# jr-support_v3.net
KiCad netlist of a schematic drawn in EAGLE
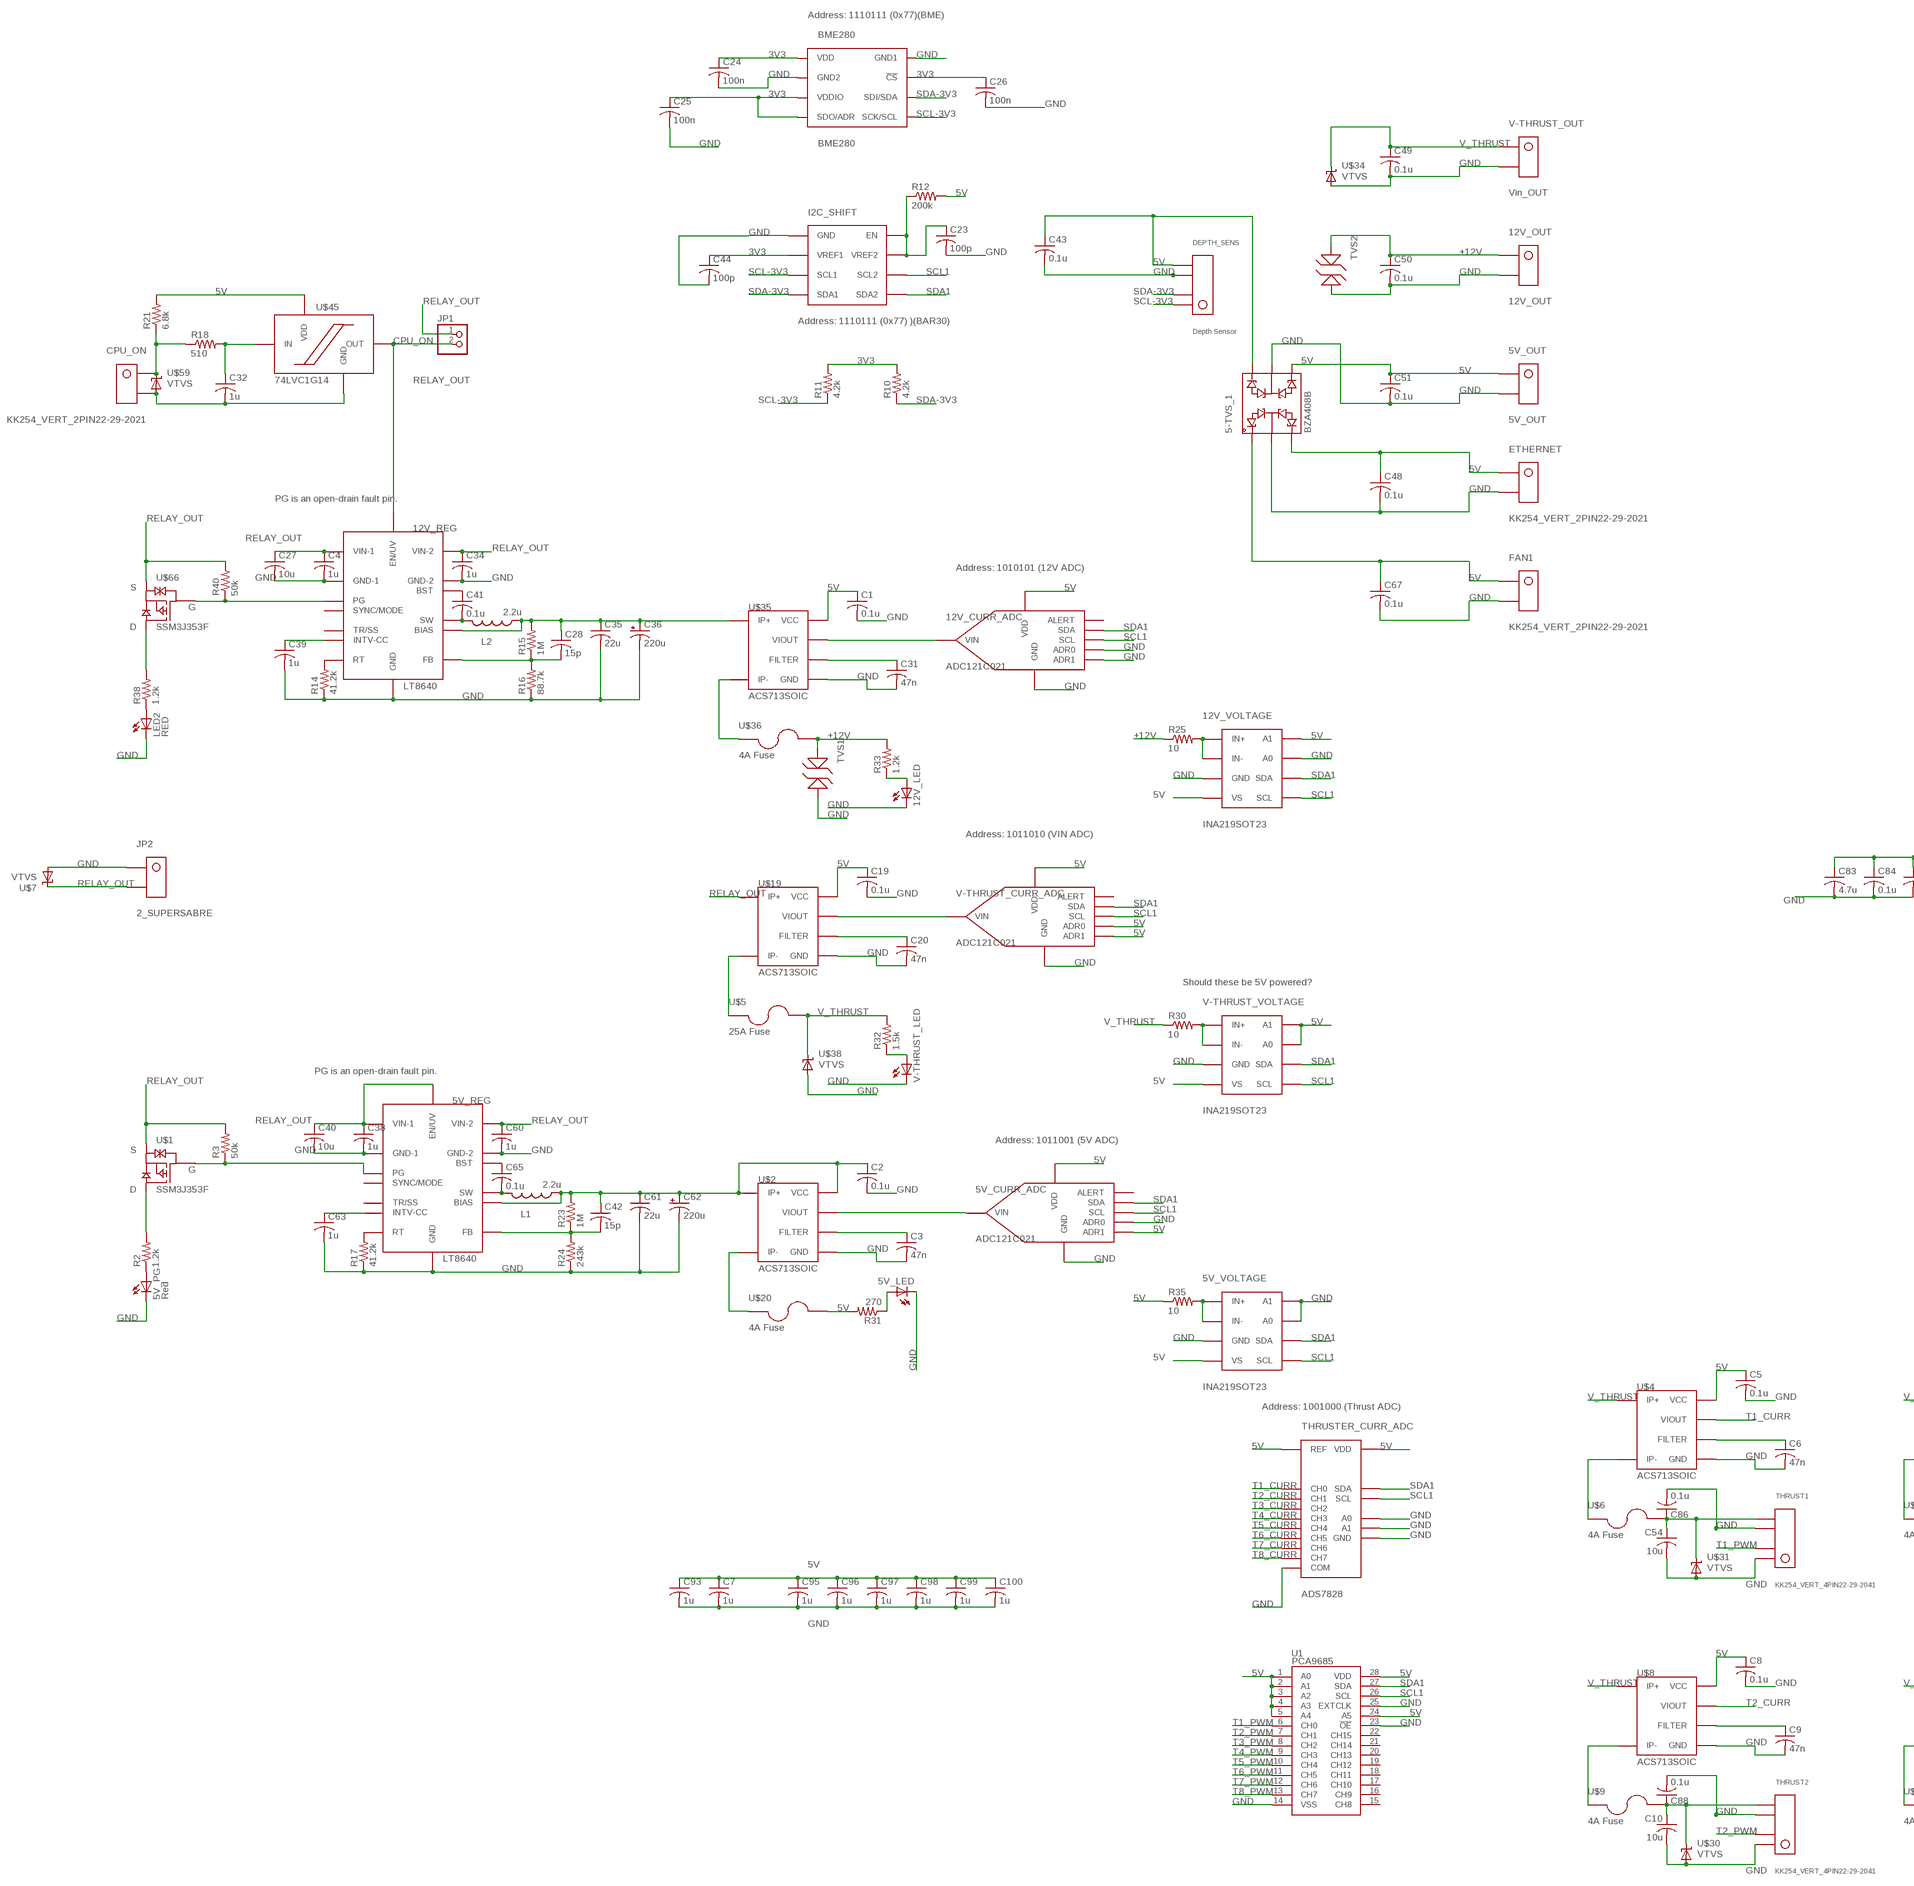
[diagram p0: schematic, sheet 1, part 1 of 2]
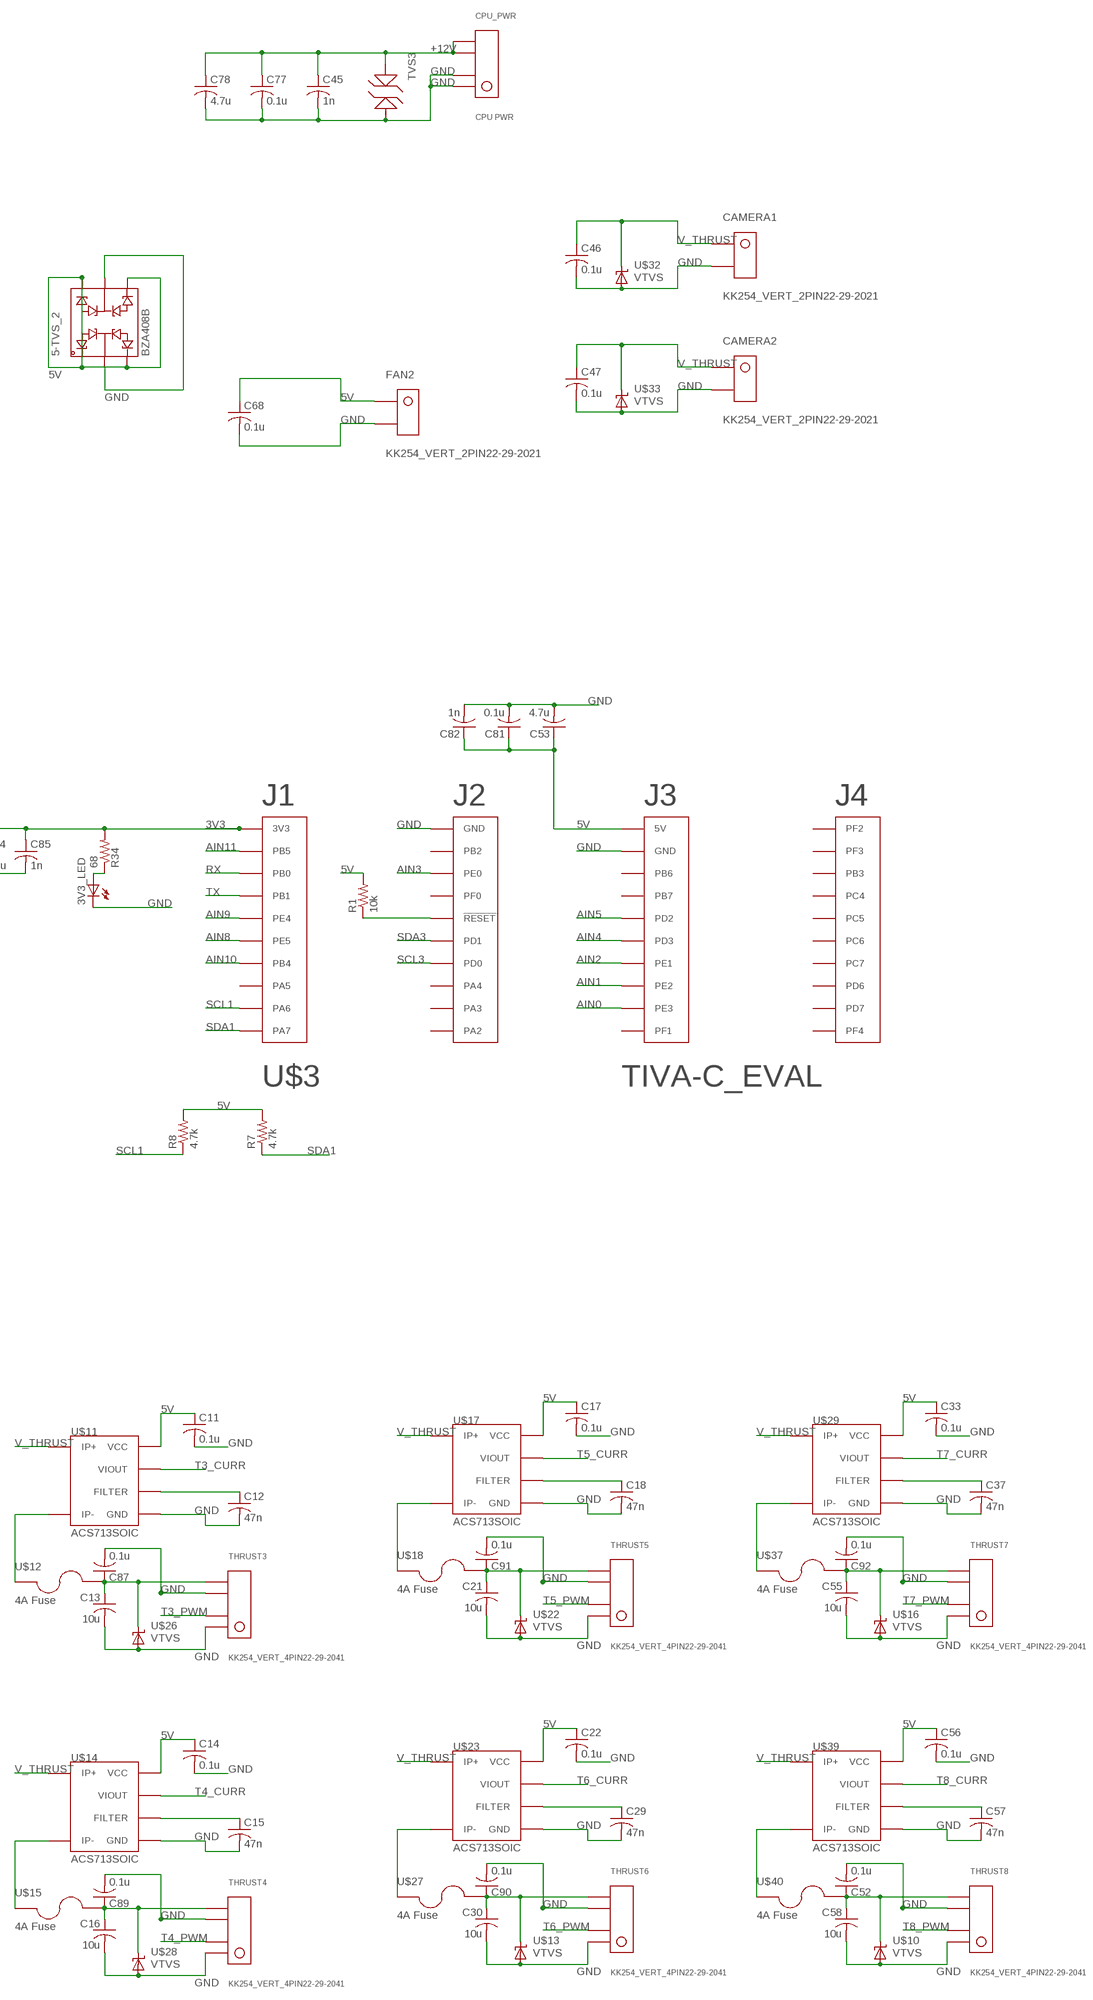
[diagram p1: schematic, sheet 1, part 2 of 2]

(export (version "E")
  (design (tool "Eeschema 10.0.6"))
  (components
    (comp (ref "3V3_LED")
      (value "0805_LED")
      (footprint "eagle-import:0805")
      (libsource (lib "eagle-import") (part "0805_LED"))
    )
    (comp (ref "5-TVS_1")
      (value "BZA408B")
      (footprint "eagle-import:SOT457")
      (libsource (lib "eagle-import") (part "BZA408B"))
    )
    (comp (ref "5-TVS_2")
      (value "BZA408B")
      (footprint "eagle-import:SOT457")
      (libsource (lib "eagle-import") (part "BZA408B"))
    )
    (comp (ref "5V_CURR_ADC")
      (value "ADC121C021")
      (footprint "eagle-import:VSSOP-8")
      (libsource (lib "eagle-import") (part "ADC121C021"))
    )
    (comp (ref "5V_LED")
      (value "0805_LED")
      (footprint "eagle-import:0805")
      (libsource (lib "eagle-import") (part "0805_LED"))
    )
    (comp (ref "5V_OUT")
      (value "5V_OUT")
      (footprint "eagle-import:KK254_VERT_2PIN")
      (libsource (lib "eagle-import") (part "KK254_VERT_2PIN22-29-2021"))
    )
    (comp (ref "5V_PG")
      (value "Red")
      (footprint "eagle-import:CHIP-LED0805")
      (libsource (lib "eagle-import") (part "LEDCHIP-LED0805"))
    )
    (comp (ref "5V_REG")
      (value "LT8640")
      (footprint "eagle-import:QFN18-3X4")
      (libsource (lib "eagle-import") (part "LT8640"))
    )
    (comp (ref "5V_VOLTAGE")
      (value "INA219SOT23")
      (footprint "eagle-import:SOT-23-8")
      (libsource (lib "eagle-import") (part "INA219SOT23"))
    )
    (comp (ref "12V_CURR_ADC")
      (value "ADC121C021")
      (footprint "eagle-import:VSSOP-8")
      (libsource (lib "eagle-import") (part "ADC121C021"))
    )
    (comp (ref "12V_LED")
      (value "0805_LED")
      (footprint "eagle-import:0805")
      (libsource (lib "eagle-import") (part "0805_LED"))
    )
    (comp (ref "12V_OUT")
      (value "12V_OUT")
      (footprint "eagle-import:KK254_VERT_2PIN")
      (libsource (lib "eagle-import") (part "KK254_VERT_2PIN22-29-2021"))
    )
    (comp (ref "12V_REG")
      (value "LT8640")
      (footprint "eagle-import:QFN18-3X4")
      (libsource (lib "eagle-import") (part "LT8640"))
    )
    (comp (ref "12V_VOLTAGE")
      (value "INA219SOT23")
      (footprint "eagle-import:SOT-23-8")
      (libsource (lib "eagle-import") (part "INA219SOT23"))
    )
    (comp (ref "BME280")
      (value "BME280")
      (footprint "eagle-import:BME280_LGA")
      (libsource (lib "eagle-import") (part "BME280"))
    )
    (comp (ref "C1")
      (value "0.1u")
      (footprint "eagle-import:C0805")
      (libsource (lib "eagle-import") (part "C-USC0805"))
    )
    (comp (ref "C2")
      (value "0.1u")
      (footprint "eagle-import:C0805")
      (libsource (lib "eagle-import") (part "C-USC0805"))
    )
    (comp (ref "C3")
      (value "47n")
      (footprint "eagle-import:C0805")
      (libsource (lib "eagle-import") (part "C-USC0805"))
    )
    (comp (ref "C4")
      (value "1u")
      (footprint "eagle-import:C0805")
      (libsource (lib "eagle-import") (part "C-USC0805"))
    )
    (comp (ref "C5")
      (value "0.1u")
      (footprint "eagle-import:C0805")
      (libsource (lib "eagle-import") (part "C-USC0805"))
    )
    (comp (ref "C6")
      (value "47n")
      (footprint "eagle-import:C0805")
      (libsource (lib "eagle-import") (part "C-USC0805"))
    )
    (comp (ref "C7")
      (value "1u")
      (footprint "eagle-import:C0805")
      (libsource (lib "eagle-import") (part "C-USC0805"))
    )
    (comp (ref "C8")
      (value "0.1u")
      (footprint "eagle-import:C0805")
      (libsource (lib "eagle-import") (part "C-USC0805"))
    )
    (comp (ref "C9")
      (value "47n")
      (footprint "eagle-import:C0805")
      (libsource (lib "eagle-import") (part "C-USC0805"))
    )
    (comp (ref "C10")
      (value "10u")
      (footprint "eagle-import:C0805")
      (libsource (lib "eagle-import") (part "C-USC0805"))
    )
    (comp (ref "C11")
      (value "0.1u")
      (footprint "eagle-import:C0805")
      (libsource (lib "eagle-import") (part "C-USC0805"))
    )
    (comp (ref "C12")
      (value "47n")
      (footprint "eagle-import:C0805")
      (libsource (lib "eagle-import") (part "C-USC0805"))
    )
    (comp (ref "C13")
      (value "10u")
      (footprint "eagle-import:C0805")
      (libsource (lib "eagle-import") (part "C-USC0805"))
    )
    (comp (ref "C14")
      (value "0.1u")
      (footprint "eagle-import:C0805")
      (libsource (lib "eagle-import") (part "C-USC0805"))
    )
    (comp (ref "C15")
      (value "47n")
      (footprint "eagle-import:C0805")
      (libsource (lib "eagle-import") (part "C-USC0805"))
    )
    (comp (ref "C16")
      (value "10u")
      (footprint "eagle-import:C0805")
      (libsource (lib "eagle-import") (part "C-USC0805"))
    )
    (comp (ref "C17")
      (value "0.1u")
      (footprint "eagle-import:C0805")
      (libsource (lib "eagle-import") (part "C-USC0805"))
    )
    (comp (ref "C18")
      (value "47n")
      (footprint "eagle-import:C0805")
      (libsource (lib "eagle-import") (part "C-USC0805"))
    )
    (comp (ref "C19")
      (value "0.1u")
      (footprint "eagle-import:C0805")
      (libsource (lib "eagle-import") (part "C-USC0805"))
    )
    (comp (ref "C20")
      (value "47n")
      (footprint "eagle-import:C0805")
      (libsource (lib "eagle-import") (part "C-USC0805"))
    )
    (comp (ref "C21")
      (value "10u")
      (footprint "eagle-import:C0805")
      (libsource (lib "eagle-import") (part "C-USC0805"))
    )
    (comp (ref "C22")
      (value "0.1u")
      (footprint "eagle-import:C0805")
      (libsource (lib "eagle-import") (part "C-USC0805"))
    )
    (comp (ref "C23")
      (value "100p")
      (footprint "eagle-import:C0805")
      (libsource (lib "eagle-import") (part "C-USC0805"))
    )
    (comp (ref "C24")
      (value "100n")
      (footprint "eagle-import:C0805")
      (libsource (lib "eagle-import") (part "C-USC0805"))
    )
    (comp (ref "C25")
      (value "100n")
      (footprint "eagle-import:C0805")
      (libsource (lib "eagle-import") (part "C-USC0805"))
    )
    (comp (ref "C26")
      (value "100n")
      (footprint "eagle-import:C0805")
      (libsource (lib "eagle-import") (part "C-USC0805"))
    )
    (comp (ref "C27")
      (value "10u")
      (footprint "eagle-import:C0805")
      (libsource (lib "eagle-import") (part "C-USC0805"))
    )
    (comp (ref "C28")
      (value "15p")
      (footprint "eagle-import:C0805")
      (libsource (lib "eagle-import") (part "C-USC0805"))
    )
    (comp (ref "C29")
      (value "47n")
      (footprint "eagle-import:C0805")
      (libsource (lib "eagle-import") (part "C-USC0805"))
    )
    (comp (ref "C30")
      (value "10u")
      (footprint "eagle-import:C0805")
      (libsource (lib "eagle-import") (part "C-USC0805"))
    )
    (comp (ref "C31")
      (value "47n")
      (footprint "eagle-import:C0805")
      (libsource (lib "eagle-import") (part "C-USC0805"))
    )
    (comp (ref "C32")
      (value "1u")
      (footprint "eagle-import:C0805")
      (libsource (lib "eagle-import") (part "C-USC0805"))
    )
    (comp (ref "C33")
      (value "0.1u")
      (footprint "eagle-import:C0805")
      (libsource (lib "eagle-import") (part "C-USC0805"))
    )
    (comp (ref "C34")
      (value "1u")
      (footprint "eagle-import:C0805")
      (libsource (lib "eagle-import") (part "C-USC0805"))
    )
    (comp (ref "C35")
      (value "22u")
      (footprint "eagle-import:C0805")
      (libsource (lib "eagle-import") (part "C-USC0805"))
    )
    (comp (ref "C36")
      (value "220u")
      (footprint "eagle-import:C-F80")
      (libsource (lib "eagle-import") (part "CPOL-USC-F80"))
    )
    (comp (ref "C37")
      (value "47n")
      (footprint "eagle-import:C0805")
      (libsource (lib "eagle-import") (part "C-USC0805"))
    )
    (comp (ref "C38")
      (value "1u")
      (footprint "eagle-import:C0805")
      (libsource (lib "eagle-import") (part "C-USC0805"))
    )
    (comp (ref "C39")
      (value "1u")
      (footprint "eagle-import:C0805")
      (libsource (lib "eagle-import") (part "C-USC0805"))
    )
    (comp (ref "C40")
      (value "10u")
      (footprint "eagle-import:C0805")
      (libsource (lib "eagle-import") (part "C-USC0805"))
    )
    (comp (ref "C41")
      (value "0.1u")
      (footprint "eagle-import:C0805")
      (libsource (lib "eagle-import") (part "C-USC0805"))
    )
    (comp (ref "C42")
      (value "15p")
      (footprint "eagle-import:C0805")
      (libsource (lib "eagle-import") (part "C-USC0805"))
    )
    (comp (ref "C43")
      (value "0.1u")
      (footprint "eagle-import:C0805")
      (libsource (lib "eagle-import") (part "C-USC0805"))
    )
    (comp (ref "C44")
      (value "100p")
      (footprint "eagle-import:C0805")
      (libsource (lib "eagle-import") (part "C-USC0805"))
    )
    (comp (ref "C45")
      (value "1n")
      (footprint "eagle-import:C0805")
      (libsource (lib "eagle-import") (part "C-USC0805"))
    )
    (comp (ref "C46")
      (value "0.1u")
      (footprint "eagle-import:C0805")
      (libsource (lib "eagle-import") (part "C-USC0805"))
    )
    (comp (ref "C47")
      (value "0.1u")
      (footprint "eagle-import:C0805")
      (libsource (lib "eagle-import") (part "C-USC0805"))
    )
    (comp (ref "C48")
      (value "0.1u")
      (footprint "eagle-import:C0805")
      (libsource (lib "eagle-import") (part "C-USC0805"))
    )
    (comp (ref "C49")
      (value "0.1u")
      (footprint "eagle-import:C0805")
      (libsource (lib "eagle-import") (part "C-USC0805"))
    )
    (comp (ref "C50")
      (value "0.1u")
      (footprint "eagle-import:C0805")
      (libsource (lib "eagle-import") (part "C-USC0805"))
    )
    (comp (ref "C51")
      (value "0.1u")
      (footprint "eagle-import:C0805")
      (libsource (lib "eagle-import") (part "C-USC0805"))
    )
    (comp (ref "C52")
      (value "0.1u")
      (footprint "eagle-import:C0805")
      (libsource (lib "eagle-import") (part "C-USC0805"))
    )
    (comp (ref "C53")
      (value "4.7u")
      (footprint "eagle-import:C0805")
      (libsource (lib "eagle-import") (part "C-USC0805"))
    )
    (comp (ref "C54")
      (value "10u")
      (footprint "eagle-import:C0805")
      (libsource (lib "eagle-import") (part "C-USC0805"))
    )
    (comp (ref "C55")
      (value "10u")
      (footprint "eagle-import:C0805")
      (libsource (lib "eagle-import") (part "C-USC0805"))
    )
    (comp (ref "C56")
      (value "0.1u")
      (footprint "eagle-import:C0805")
      (libsource (lib "eagle-import") (part "C-USC0805"))
    )
    (comp (ref "C57")
      (value "47n")
      (footprint "eagle-import:C0805")
      (libsource (lib "eagle-import") (part "C-USC0805"))
    )
    (comp (ref "C58")
      (value "10u")
      (footprint "eagle-import:C0805")
      (libsource (lib "eagle-import") (part "C-USC0805"))
    )
    (comp (ref "C60")
      (value "1u")
      (footprint "eagle-import:C0805")
      (libsource (lib "eagle-import") (part "C-USC0805"))
    )
    (comp (ref "C61")
      (value "22u")
      (footprint "eagle-import:C0805")
      (libsource (lib "eagle-import") (part "C-USC0805"))
    )
    (comp (ref "C62")
      (value "220u")
      (footprint "eagle-import:C-F80")
      (libsource (lib "eagle-import") (part "CPOL-USC-F80"))
    )
    (comp (ref "C63")
      (value "1u")
      (footprint "eagle-import:C0805")
      (libsource (lib "eagle-import") (part "C-USC0805"))
    )
    (comp (ref "C65")
      (value "0.1u")
      (footprint "eagle-import:C0805")
      (libsource (lib "eagle-import") (part "C-USC0805"))
    )
    (comp (ref "C67")
      (value "0.1u")
      (footprint "eagle-import:C0805")
      (libsource (lib "eagle-import") (part "C-USC0805"))
    )
    (comp (ref "C68")
      (value "0.1u")
      (footprint "eagle-import:C0805")
      (libsource (lib "eagle-import") (part "C-USC0805"))
    )
    (comp (ref "C77")
      (value "0.1u")
      (footprint "eagle-import:C0805")
      (libsource (lib "eagle-import") (part "C-USC0805"))
    )
    (comp (ref "C78")
      (value "4.7u")
      (footprint "eagle-import:C0805")
      (libsource (lib "eagle-import") (part "C-USC0805"))
    )
    (comp (ref "C81")
      (value "0.1u")
      (footprint "eagle-import:C0805")
      (libsource (lib "eagle-import") (part "C-USC0805"))
    )
    (comp (ref "C82")
      (value "1n")
      (footprint "eagle-import:C0805")
      (libsource (lib "eagle-import") (part "C-USC0805"))
    )
    (comp (ref "C83")
      (value "4.7u")
      (footprint "eagle-import:C0805")
      (libsource (lib "eagle-import") (part "C-USC0805"))
    )
    (comp (ref "C84")
      (value "0.1u")
      (footprint "eagle-import:C0805")
      (libsource (lib "eagle-import") (part "C-USC0805"))
    )
    (comp (ref "C85")
      (value "1n")
      (footprint "eagle-import:C0805")
      (libsource (lib "eagle-import") (part "C-USC0805"))
    )
    (comp (ref "C86")
      (value "0.1u")
      (footprint "eagle-import:C0805")
      (libsource (lib "eagle-import") (part "C-USC0805"))
    )
    (comp (ref "C87")
      (value "0.1u")
      (footprint "eagle-import:C0805")
      (libsource (lib "eagle-import") (part "C-USC0805"))
    )
    (comp (ref "C88")
      (value "0.1u")
      (footprint "eagle-import:C0805")
      (libsource (lib "eagle-import") (part "C-USC0805"))
    )
    (comp (ref "C89")
      (value "0.1u")
      (footprint "eagle-import:C0805")
      (libsource (lib "eagle-import") (part "C-USC0805"))
    )
    (comp (ref "C90")
      (value "0.1u")
      (footprint "eagle-import:C0805")
      (libsource (lib "eagle-import") (part "C-USC0805"))
    )
    (comp (ref "C91")
      (value "0.1u")
      (footprint "eagle-import:C0805")
      (libsource (lib "eagle-import") (part "C-USC0805"))
    )
    (comp (ref "C92")
      (value "0.1u")
      (footprint "eagle-import:C0805")
      (libsource (lib "eagle-import") (part "C-USC0805"))
    )
    (comp (ref "C93")
      (value "1u")
      (footprint "eagle-import:C0805")
      (libsource (lib "eagle-import") (part "C-USC0805"))
    )
    (comp (ref "C95")
      (value "1u")
      (footprint "eagle-import:C0805")
      (libsource (lib "eagle-import") (part "C-USC0805"))
    )
    (comp (ref "C96")
      (value "1u")
      (footprint "eagle-import:C0805")
      (libsource (lib "eagle-import") (part "C-USC0805"))
    )
    (comp (ref "C97")
      (value "1u")
      (footprint "eagle-import:C0805")
      (libsource (lib "eagle-import") (part "C-USC0805"))
    )
    (comp (ref "C98")
      (value "1u")
      (footprint "eagle-import:C0805")
      (libsource (lib "eagle-import") (part "C-USC0805"))
    )
    (comp (ref "C99")
      (value "1u")
      (footprint "eagle-import:C0805")
      (libsource (lib "eagle-import") (part "C-USC0805"))
    )
    (comp (ref "C100")
      (value "1u")
      (footprint "eagle-import:C0805")
      (libsource (lib "eagle-import") (part "C-USC0805"))
    )
    (comp (ref "CAMERA1")
      (value "KK254_VERT_2PIN22-29-2021")
      (footprint "eagle-import:KK254_VERT_2PIN")
      (libsource (lib "eagle-import") (part "KK254_VERT_2PIN22-29-2021"))
    )
    (comp (ref "CAMERA2")
      (value "KK254_VERT_2PIN22-29-2021")
      (footprint "eagle-import:KK254_VERT_2PIN")
      (libsource (lib "eagle-import") (part "KK254_VERT_2PIN22-29-2021"))
    )
    (comp (ref "CPU_ON")
      (value "KK254_VERT_2PIN22-29-2021")
      (footprint "eagle-import:KK254_VERT_2PIN")
      (libsource (lib "eagle-import") (part "KK254_VERT_2PIN22-29-2021"))
    )
    (comp (ref "CPU_PWR")
      (value "CPU PWR")
      (footprint "eagle-import:KK254_VERT_4PIN")
      (libsource (lib "eagle-import") (part "KK254_VERT_4PIN22-29-2041"))
    )
    (comp (ref "DEPTH_SENS")
      (value "Depth Sensor")
      (footprint "eagle-import:KK254_VERT_4PIN")
      (libsource (lib "eagle-import") (part "KK254_VERT_4PIN22-29-2041"))
    )
    (comp (ref "ETHERNET")
      (value "KK254_VERT_2PIN22-29-2021")
      (footprint "eagle-import:KK254_VERT_2PIN")
      (libsource (lib "eagle-import") (part "KK254_VERT_2PIN22-29-2021"))
    )
    (comp (ref "FAN1")
      (value "KK254_VERT_2PIN22-29-2021")
      (footprint "eagle-import:KK254_VERT_2PIN")
      (libsource (lib "eagle-import") (part "KK254_VERT_2PIN22-29-2021"))
    )
    (comp (ref "FAN2")
      (value "KK254_VERT_2PIN22-29-2021")
      (footprint "eagle-import:KK254_VERT_2PIN")
      (libsource (lib "eagle-import") (part "KK254_VERT_2PIN22-29-2021"))
    )
    (comp (ref "I2C_SHIFT")
      (value "PCA9306DCT")
      (footprint "eagle-import:SM8")
      (libsource (lib "eagle-import") (part "PCA9306DCT"))
    )
    (comp (ref "JP1")
      (value "PINHD-1X2")
      (footprint "eagle-import:1X02")
      (libsource (lib "eagle-import") (part "PINHD-1X2"))
    )
    (comp (ref "JP2")
      (value "2_SUPERSABRE")
      (footprint "eagle-import:SUPERSABRE_2CIRCUIT")
      (libsource (lib "eagle-import") (part "2_SUPERSABRE"))
    )
    (comp (ref "L1")
      (value "2.2u")
      (footprint "eagle-import:L0740")
      (libsource (lib "eagle-import") (part "L-USL0740"))
    )
    (comp (ref "L2")
      (value "2.2u")
      (footprint "eagle-import:L0740")
      (libsource (lib "eagle-import") (part "L-USL0740"))
    )
    (comp (ref "LED2")
      (value "RED")
      (footprint "eagle-import:CHIP-LED0805")
      (libsource (lib "eagle-import") (part "LEDCHIP-LED0805"))
    )
    (comp (ref "R1")
      (value "10k")
      (footprint "eagle-import:R0805")
      (libsource (lib "eagle-import") (part "R-US_R0805"))
    )
    (comp (ref "R2")
      (value "1.2k")
      (footprint "eagle-import:R0805")
      (libsource (lib "eagle-import") (part "R-US_R0805"))
    )
    (comp (ref "R3")
      (value "50k")
      (footprint "eagle-import:R0805")
      (libsource (lib "eagle-import") (part "R-US_R0805"))
    )
    (comp (ref "R7")
      (value "4.7k")
      (footprint "eagle-import:R0805")
      (libsource (lib "eagle-import") (part "R-US_R0805"))
    )
    (comp (ref "R8")
      (value "4.7k")
      (footprint "eagle-import:R0805")
      (libsource (lib "eagle-import") (part "R-US_R0805"))
    )
    (comp (ref "R10")
      (value "4.2k")
      (footprint "eagle-import:R0805")
      (libsource (lib "eagle-import") (part "R-US_R0805"))
    )
    (comp (ref "R11")
      (value "4.2k")
      (footprint "eagle-import:R0805")
      (libsource (lib "eagle-import") (part "R-US_R0805"))
    )
    (comp (ref "R12")
      (value "200k")
      (footprint "eagle-import:R0805")
      (libsource (lib "eagle-import") (part "R-US_R0805"))
    )
    (comp (ref "R14")
      (value "41.2k")
      (footprint "eagle-import:R0805")
      (libsource (lib "eagle-import") (part "R-US_R0805"))
    )
    (comp (ref "R15")
      (value "1M")
      (footprint "eagle-import:R0805")
      (libsource (lib "eagle-import") (part "R-US_R0805"))
    )
    (comp (ref "R16")
      (value "88.7k")
      (footprint "eagle-import:R0805")
      (libsource (lib "eagle-import") (part "R-US_R0805"))
    )
    (comp (ref "R17")
      (value "41.2k")
      (footprint "eagle-import:R0805")
      (libsource (lib "eagle-import") (part "R-US_R0805"))
    )
    (comp (ref "R18")
      (value "510")
      (footprint "eagle-import:R0805")
      (libsource (lib "eagle-import") (part "R-US_R0805"))
    )
    (comp (ref "R21")
      (value "6.8k")
      (footprint "eagle-import:R0805")
      (libsource (lib "eagle-import") (part "R-US_R0805"))
    )
    (comp (ref "R23")
      (value "1M")
      (footprint "eagle-import:R0805")
      (libsource (lib "eagle-import") (part "R-US_R0805"))
    )
    (comp (ref "R24")
      (value "243k")
      (footprint "eagle-import:R0805")
      (libsource (lib "eagle-import") (part "R-US_R0805"))
    )
    (comp (ref "R25")
      (value "10")
      (footprint "eagle-import:R0805")
      (libsource (lib "eagle-import") (part "R-US_R0805"))
    )
    (comp (ref "R30")
      (value "10")
      (footprint "eagle-import:R0805")
      (libsource (lib "eagle-import") (part "R-US_R0805"))
    )
    (comp (ref "R31")
      (value "270")
      (footprint "eagle-import:R0805")
      (libsource (lib "eagle-import") (part "R-US_R0805"))
    )
    (comp (ref "R32")
      (value "1.5k")
      (footprint "eagle-import:R0805")
      (libsource (lib "eagle-import") (part "R-US_R0805"))
    )
    (comp (ref "R33")
      (value "1.2k")
      (footprint "eagle-import:R0805")
      (libsource (lib "eagle-import") (part "R-US_R0805"))
    )
    (comp (ref "R34")
      (value "68")
      (footprint "eagle-import:R0805")
      (libsource (lib "eagle-import") (part "R-US_R0805"))
    )
    (comp (ref "R35")
      (value "10")
      (footprint "eagle-import:R0805")
      (libsource (lib "eagle-import") (part "R-US_R0805"))
    )
    (comp (ref "R38")
      (value "1.2k")
      (footprint "eagle-import:R0805")
      (libsource (lib "eagle-import") (part "R-US_R0805"))
    )
    (comp (ref "R40")
      (value "50k")
      (footprint "eagle-import:R0805")
      (libsource (lib "eagle-import") (part "R-US_R0805"))
    )
    (comp (ref "THRUST1")
      (value "KK254_VERT_4PIN22-29-2041")
      (footprint "eagle-import:KK254_VERT_4PIN")
      (libsource (lib "eagle-import") (part "KK254_VERT_4PIN22-29-2041"))
    )
    (comp (ref "THRUST2")
      (value "KK254_VERT_4PIN22-29-2041")
      (footprint "eagle-import:KK254_VERT_4PIN")
      (libsource (lib "eagle-import") (part "KK254_VERT_4PIN22-29-2041"))
    )
    (comp (ref "THRUST3")
      (value "KK254_VERT_4PIN22-29-2041")
      (footprint "eagle-import:KK254_VERT_4PIN")
      (libsource (lib "eagle-import") (part "KK254_VERT_4PIN22-29-2041"))
    )
    (comp (ref "THRUST4")
      (value "KK254_VERT_4PIN22-29-2041")
      (footprint "eagle-import:KK254_VERT_4PIN")
      (libsource (lib "eagle-import") (part "KK254_VERT_4PIN22-29-2041"))
    )
    (comp (ref "THRUST5")
      (value "KK254_VERT_4PIN22-29-2041")
      (footprint "eagle-import:KK254_VERT_4PIN")
      (libsource (lib "eagle-import") (part "KK254_VERT_4PIN22-29-2041"))
    )
    (comp (ref "THRUST6")
      (value "KK254_VERT_4PIN22-29-2041")
      (footprint "eagle-import:KK254_VERT_4PIN")
      (libsource (lib "eagle-import") (part "KK254_VERT_4PIN22-29-2041"))
    )
    (comp (ref "THRUST7")
      (value "KK254_VERT_4PIN22-29-2041")
      (footprint "eagle-import:KK254_VERT_4PIN")
      (libsource (lib "eagle-import") (part "KK254_VERT_4PIN22-29-2041"))
    )
    (comp (ref "THRUST8")
      (value "KK254_VERT_4PIN22-29-2041")
      (footprint "eagle-import:KK254_VERT_4PIN")
      (libsource (lib "eagle-import") (part "KK254_VERT_4PIN22-29-2041"))
    )
    (comp (ref "THRUSTER_CURR_ADC")
      (value "ADS7828")
      (footprint "eagle-import:TSSOP16")
      (libsource (lib "eagle-import") (part "ADS7828"))
    )
    (comp (ref "TVS1")
      (value "ESD12VD3B")
      (footprint "eagle-import:SOD-323")
      (libsource (lib "eagle-import") (part "ESD12VD3B"))
    )
    (comp (ref "TVS2")
      (value "ESD12VD3B")
      (footprint "eagle-import:SOD-323")
      (libsource (lib "eagle-import") (part "ESD12VD3B"))
    )
    (comp (ref "TVS3")
      (value "ESD12VD3B")
      (footprint "eagle-import:SOD-323")
      (libsource (lib "eagle-import") (part "ESD12VD3B"))
    )
    (comp (ref "U$1")
      (value "SSM3J353F")
      (footprint "eagle-import:SOT-346-3_S-MINI")
      (libsource (lib "eagle-import") (part "SSM3J353F"))
    )
    (comp (ref "U$2")
      (value "ACS713SOIC")
      (footprint "eagle-import:ACS713-SOIC")
      (libsource (lib "eagle-import") (part "ACS713SOIC"))
    )
    (comp (ref "U$3")
      (value "TIVA-C_EVAL")
      (footprint "eagle-import:TIVA-C_EVAL")
      (libsource (lib "eagle-import") (part "TIVA-C_EVAL"))
    )
    (comp (ref "U$4")
      (value "ACS713SOIC")
      (footprint "eagle-import:ACS713-SOIC")
      (libsource (lib "eagle-import") (part "ACS713SOIC"))
    )
    (comp (ref "U$5")
      (value "25A Fuse")
      (footprint "eagle-import:1.25__FUSECLIPS")
      (libsource (lib "eagle-import") (part "BOWED-1.25{dblquote}-FUSECLIPS"))
    )
    (comp (ref "U$6")
      (value "4A Fuse")
      (footprint "eagle-import:154-OMNI-BLOK")
      (libsource (lib "eagle-import") (part "154-OMNI_BLOK"))
    )
    (comp (ref "U$7")
      (value "VTVS")
      (footprint "eagle-import:DO-219AB")
      (libsource (lib "eagle-import") (part "VTVS"))
    )
    (comp (ref "U$8")
      (value "ACS713SOIC")
      (footprint "eagle-import:ACS713-SOIC")
      (libsource (lib "eagle-import") (part "ACS713SOIC"))
    )
    (comp (ref "U$9")
      (value "4A Fuse")
      (footprint "eagle-import:154-OMNI-BLOK")
      (libsource (lib "eagle-import") (part "154-OMNI_BLOK"))
    )
    (comp (ref "U$10")
      (value "VTVS")
      (footprint "eagle-import:DO-219AB")
      (libsource (lib "eagle-import") (part "VTVS"))
    )
    (comp (ref "U$11")
      (value "ACS713SOIC")
      (footprint "eagle-import:ACS713-SOIC")
      (libsource (lib "eagle-import") (part "ACS713SOIC"))
    )
    (comp (ref "U$12")
      (value "4A Fuse")
      (footprint "eagle-import:154-OMNI-BLOK")
      (libsource (lib "eagle-import") (part "154-OMNI_BLOK"))
    )
    (comp (ref "U$13")
      (value "VTVS")
      (footprint "eagle-import:DO-219AB")
      (libsource (lib "eagle-import") (part "VTVS"))
    )
    (comp (ref "U$14")
      (value "ACS713SOIC")
      (footprint "eagle-import:ACS713-SOIC")
      (libsource (lib "eagle-import") (part "ACS713SOIC"))
    )
    (comp (ref "U$15")
      (value "4A Fuse")
      (footprint "eagle-import:154-OMNI-BLOK")
      (libsource (lib "eagle-import") (part "154-OMNI_BLOK"))
    )
    (comp (ref "U$16")
      (value "VTVS")
      (footprint "eagle-import:DO-219AB")
      (libsource (lib "eagle-import") (part "VTVS"))
    )
    (comp (ref "U$17")
      (value "ACS713SOIC")
      (footprint "eagle-import:ACS713-SOIC")
      (libsource (lib "eagle-import") (part "ACS713SOIC"))
    )
    (comp (ref "U$18")
      (value "4A Fuse")
      (footprint "eagle-import:154-OMNI-BLOK")
      (libsource (lib "eagle-import") (part "154-OMNI_BLOK"))
    )
    (comp (ref "U$19")
      (value "ACS713SOIC")
      (footprint "eagle-import:ACS713-SOIC")
      (libsource (lib "eagle-import") (part "ACS713SOIC"))
    )
    (comp (ref "U$20")
      (value "4A Fuse")
      (footprint "eagle-import:154-OMNI-BLOK")
      (libsource (lib "eagle-import") (part "154-OMNI_BLOK"))
    )
    (comp (ref "U$22")
      (value "VTVS")
      (footprint "eagle-import:DO-219AB")
      (libsource (lib "eagle-import") (part "VTVS"))
    )
    (comp (ref "U$23")
      (value "ACS713SOIC")
      (footprint "eagle-import:ACS713-SOIC")
      (libsource (lib "eagle-import") (part "ACS713SOIC"))
    )
    (comp (ref "U$26")
      (value "VTVS")
      (footprint "eagle-import:DO-219AB")
      (libsource (lib "eagle-import") (part "VTVS"))
    )
    (comp (ref "U$27")
      (value "4A Fuse")
      (footprint "eagle-import:154-OMNI-BLOK")
      (libsource (lib "eagle-import") (part "154-OMNI_BLOK"))
    )
    (comp (ref "U$28")
      (value "VTVS")
      (footprint "eagle-import:DO-219AB")
      (libsource (lib "eagle-import") (part "VTVS"))
    )
    (comp (ref "U$29")
      (value "ACS713SOIC")
      (footprint "eagle-import:ACS713-SOIC")
      (libsource (lib "eagle-import") (part "ACS713SOIC"))
    )
    (comp (ref "U$30")
      (value "VTVS")
      (footprint "eagle-import:DO-219AB")
      (libsource (lib "eagle-import") (part "VTVS"))
    )
    (comp (ref "U$31")
      (value "VTVS")
      (footprint "eagle-import:DO-219AB")
      (libsource (lib "eagle-import") (part "VTVS"))
    )
    (comp (ref "U$32")
      (value "VTVS")
      (footprint "eagle-import:DO-219AB")
      (libsource (lib "eagle-import") (part "VTVS"))
    )
    (comp (ref "U$33")
      (value "VTVS")
      (footprint "eagle-import:DO-219AB")
      (libsource (lib "eagle-import") (part "VTVS"))
    )
    (comp (ref "U$34")
      (value "VTVS")
      (footprint "eagle-import:DO-219AB")
      (libsource (lib "eagle-import") (part "VTVS"))
    )
    (comp (ref "U$35")
      (value "ACS713SOIC")
      (footprint "eagle-import:ACS713-SOIC")
      (libsource (lib "eagle-import") (part "ACS713SOIC"))
    )
    (comp (ref "U$36")
      (value "4A Fuse")
      (footprint "eagle-import:154-OMNI-BLOK")
      (libsource (lib "eagle-import") (part "154-OMNI_BLOK"))
    )
    (comp (ref "U$37")
      (value "4A Fuse")
      (footprint "eagle-import:154-OMNI-BLOK")
      (libsource (lib "eagle-import") (part "154-OMNI_BLOK"))
    )
    (comp (ref "U$38")
      (value "VTVS")
      (footprint "eagle-import:DO-219AB")
      (libsource (lib "eagle-import") (part "VTVS"))
    )
    (comp (ref "U$39")
      (value "ACS713SOIC")
      (footprint "eagle-import:ACS713-SOIC")
      (libsource (lib "eagle-import") (part "ACS713SOIC"))
    )
    (comp (ref "U$40")
      (value "4A Fuse")
      (footprint "eagle-import:154-OMNI-BLOK")
      (libsource (lib "eagle-import") (part "154-OMNI_BLOK"))
    )
    (comp (ref "U$45")
      (value "74LVC1G14")
      (footprint "eagle-import:TSSOP5")
      (libsource (lib "eagle-import") (part "74LVC1G14"))
    )
    (comp (ref "U$59")
      (value "VTVS")
      (footprint "eagle-import:DO-219AB")
      (libsource (lib "eagle-import") (part "VTVS"))
    )
    (comp (ref "U$66")
      (value "SSM3J353F")
      (footprint "eagle-import:SOT-346-3_S-MINI")
      (libsource (lib "eagle-import") (part "SSM3J353F"))
    )
    (comp (ref "U1")
      (value "PCA9685")
      (footprint "eagle-import:TSSOP-28_4MM")
      (libsource (lib "eagle-import") (part "PCA9685"))
    )
    (comp (ref "V-THRUST_CURR_ADC")
      (value "ADC121C021")
      (footprint "eagle-import:VSSOP-8")
      (libsource (lib "eagle-import") (part "ADC121C021"))
    )
    (comp (ref "V-THRUST_LED")
      (value "0805_LED")
      (footprint "eagle-import:0805")
      (libsource (lib "eagle-import") (part "0805_LED"))
    )
    (comp (ref "V-THRUST_OUT")
      (value "Vin_OUT")
      (footprint "eagle-import:KK254_VERT_2PIN")
      (libsource (lib "eagle-import") (part "KK254_VERT_2PIN22-29-2021"))
    )
    (comp (ref "V-THRUST_VOLTAGE")
      (value "INA219SOT23")
      (footprint "eagle-import:SOT-23-8")
      (libsource (lib "eagle-import") (part "INA219SOT23"))
    )
  )
  (nets
    (net (code "1") (name "/+12V") (class "Default")
      (node (ref "12V_OUT") (pin "P$1") (pinfunction "P$1_P$1") (pintype "bidirectional"))
      (node (ref "C45") (pin "1") (pinfunction "1_1") (pintype "passive"))
      (node (ref "C50") (pin "1") (pinfunction "1_1") (pintype "passive"))
      (node (ref "C77") (pin "1") (pinfunction "1_1") (pintype "passive"))
      (node (ref "C78") (pin "1") (pinfunction "1_1") (pintype "passive"))
      (node (ref "CPU_PWR") (pin "P$3") (pinfunction "P$3_P$3") (pintype "bidirectional"))
      (node (ref "CPU_PWR") (pin "P$4") (pinfunction "P$4_P$4") (pintype "bidirectional"))
      (node (ref "R25") (pin "1") (pinfunction "1_1") (pintype "passive"))
      (node (ref "R33") (pin "2") (pinfunction "2_2") (pintype "passive"))
      (node (ref "TVS1") (pin "P$1") (pinfunction "P$1_P$1") (pintype "bidirectional"))
      (node (ref "TVS2") (pin "P$1") (pinfunction "P$1_P$1") (pintype "bidirectional"))
      (node (ref "TVS3") (pin "P$1") (pinfunction "P$1_P$1") (pintype "bidirectional"))
      (node (ref "U$36") (pin "P$2") (pinfunction "P$2_P$2") (pintype "bidirectional"))
    )
    (net (code "2") (name "/3V3") (class "Default")
      (node (ref "BME280") (pin "P$2") (pinfunction "~{CS}_P$2") (pintype "bidirectional"))
      (node (ref "BME280") (pin "P$5") (pinfunction "SDO/ADR_P$5") (pintype "bidirectional"))
      (node (ref "BME280") (pin "P$6") (pinfunction "VDDIO_P$6") (pintype "bidirectional"))
      (node (ref "BME280") (pin "P$8") (pinfunction "VDD_P$8") (pintype "bidirectional"))
      (node (ref "C24") (pin "1") (pinfunction "1_1") (pintype "passive"))
      (node (ref "C25") (pin "1") (pinfunction "1_1") (pintype "passive"))
      (node (ref "C26") (pin "1") (pinfunction "1_1") (pintype "passive"))
      (node (ref "C44") (pin "1") (pinfunction "1_1") (pintype "passive"))
      (node (ref "C83") (pin "1") (pinfunction "1_1") (pintype "passive"))
      (node (ref "C84") (pin "1") (pinfunction "1_1") (pintype "passive"))
      (node (ref "C85") (pin "1") (pinfunction "1_1") (pintype "passive"))
      (node (ref "I2C_SHIFT") (pin "P$2") (pinfunction "VREF1_P$2") (pintype "bidirectional"))
      (node (ref "R10") (pin "2") (pinfunction "2_2") (pintype "passive"))
      (node (ref "R11") (pin "2") (pinfunction "2_2") (pintype "passive"))
      (node (ref "R34") (pin "2") (pinfunction "2_2") (pintype "passive"))
      (node (ref "U$3") (pin "1-1") (pinfunction "3V3_1-1") (pintype "bidirectional"))
    )
    (net (code "3") (name "/5V") (class "Default")
      (node (ref "12V_CURR_ADC") (pin "P$5") (pinfunction "VDD_P$5") (pintype "bidirectional"))
      (node (ref "12V_VOLTAGE") (pin "P$4") (pinfunction "VS_P$4") (pintype "bidirectional"))
      (node (ref "12V_VOLTAGE") (pin "P$8") (pinfunction "A1_P$8") (pintype "bidirectional"))
      (node (ref "5-TVS_1") (pin "P$1") (pinfunction "P$1_P$1") (pintype "bidirectional"))
      (node (ref "5-TVS_1") (pin "P$3") (pinfunction "P$3_P$3") (pintype "bidirectional"))
      (node (ref "5-TVS_1") (pin "P$4") (pinfunction "P$4_P$4") (pintype "bidirectional"))
      (node (ref "5-TVS_1") (pin "P$6") (pinfunction "P$6_P$6") (pintype "bidirectional"))
      (node (ref "5-TVS_2") (pin "P$1") (pinfunction "P$1_P$1") (pintype "bidirectional"))
      (node (ref "5-TVS_2") (pin "P$3") (pinfunction "P$3_P$3") (pintype "bidirectional"))
      (node (ref "5-TVS_2") (pin "P$4") (pinfunction "P$4_P$4") (pintype "bidirectional"))
      (node (ref "5-TVS_2") (pin "P$6") (pinfunction "P$6_P$6") (pintype "bidirectional"))
      (node (ref "5V_CURR_ADC") (pin "P$5") (pinfunction "VDD_P$5") (pintype "bidirectional"))
      (node (ref "5V_CURR_ADC") (pin "P$6") (pinfunction "ADR1_P$6") (pintype "bidirectional"))
      (node (ref "5V_OUT") (pin "P$1") (pinfunction "P$1_P$1") (pintype "bidirectional"))
      (node (ref "5V_VOLTAGE") (pin "P$4") (pinfunction "VS_P$4") (pintype "bidirectional"))
      (node (ref "C1") (pin "1") (pinfunction "1_1") (pintype "passive"))
      (node (ref "C100") (pin "1") (pinfunction "1_1") (pintype "passive"))
      (node (ref "C11") (pin "1") (pinfunction "1_1") (pintype "passive"))
      (node (ref "C14") (pin "1") (pinfunction "1_1") (pintype "passive"))
      (node (ref "C17") (pin "1") (pinfunction "1_1") (pintype "passive"))
      (node (ref "C19") (pin "1") (pinfunction "1_1") (pintype "passive"))
      (node (ref "C22") (pin "1") (pinfunction "1_1") (pintype "passive"))
      (node (ref "C33") (pin "1") (pinfunction "1_1") (pintype "passive"))
      (node (ref "C43") (pin "1") (pinfunction "1_1") (pintype "passive"))
      (node (ref "C48") (pin "1") (pinfunction "1_1") (pintype "passive"))
      (node (ref "C5") (pin "1") (pinfunction "1_1") (pintype "passive"))
      (node (ref "C51") (pin "1") (pinfunction "1_1") (pintype "passive"))
      (node (ref "C53") (pin "1") (pinfunction "1_1") (pintype "passive"))
      (node (ref "C56") (pin "1") (pinfunction "1_1") (pintype "passive"))
      (node (ref "C67") (pin "1") (pinfunction "1_1") (pintype "passive"))
      (node (ref "C68") (pin "1") (pinfunction "1_1") (pintype "passive"))
      (node (ref "C7") (pin "1") (pinfunction "1_1") (pintype "passive"))
      (node (ref "C8") (pin "1") (pinfunction "1_1") (pintype "passive"))
      (node (ref "C81") (pin "1") (pinfunction "1_1") (pintype "passive"))
      (node (ref "C82") (pin "1") (pinfunction "1_1") (pintype "passive"))
      (node (ref "C93") (pin "1") (pinfunction "1_1") (pintype "passive"))
      (node (ref "C95") (pin "1") (pinfunction "1_1") (pintype "passive"))
      (node (ref "C96") (pin "1") (pinfunction "1_1") (pintype "passive"))
      (node (ref "C97") (pin "1") (pinfunction "1_1") (pintype "passive"))
      (node (ref "C98") (pin "1") (pinfunction "1_1") (pintype "passive"))
      (node (ref "C99") (pin "1") (pinfunction "1_1") (pintype "passive"))
      (node (ref "DEPTH_SENS") (pin "P$4") (pinfunction "P$4_P$4") (pintype "bidirectional"))
      (node (ref "ETHERNET") (pin "P$1") (pinfunction "P$1_P$1") (pintype "bidirectional"))
      (node (ref "FAN1") (pin "P$1") (pinfunction "P$1_P$1") (pintype "bidirectional"))
      (node (ref "FAN2") (pin "P$1") (pinfunction "P$1_P$1") (pintype "bidirectional"))
      (node (ref "R1") (pin "2") (pinfunction "2_2") (pintype "passive"))
      (node (ref "R12") (pin "2") (pinfunction "2_2") (pintype "passive"))
      (node (ref "R21") (pin "2") (pinfunction "2_2") (pintype "passive"))
      (node (ref "R31") (pin "2") (pinfunction "2_2") (pintype "passive"))
      (node (ref "R35") (pin "1") (pinfunction "1_1") (pintype "passive"))
      (node (ref "R7") (pin "2") (pinfunction "2_2") (pintype "passive"))
      (node (ref "R8") (pin "2") (pinfunction "2_2") (pintype "passive"))
      (node (ref "THRUSTER_CURR_ADC") (pin "10") (pinfunction "REF_10") (pintype "bidirectional"))
      (node (ref "THRUSTER_CURR_ADC") (pin "16") (pinfunction "VDD_16") (pintype "bidirectional"))
      (node (ref "U$11") (pin "P$8") (pinfunction "VCC_P$8") (pintype "bidirectional"))
      (node (ref "U$14") (pin "P$8") (pinfunction "VCC_P$8") (pintype "bidirectional"))
      (node (ref "U$17") (pin "P$8") (pinfunction "VCC_P$8") (pintype "bidirectional"))
      (node (ref "U$19") (pin "P$8") (pinfunction "VCC_P$8") (pintype "bidirectional"))
      (node (ref "U$20") (pin "P$2") (pinfunction "P$2_P$2") (pintype "bidirectional"))
      (node (ref "U$23") (pin "P$8") (pinfunction "VCC_P$8") (pintype "bidirectional"))
      (node (ref "U$29") (pin "P$8") (pinfunction "VCC_P$8") (pintype "bidirectional"))
      (node (ref "U$3") (pin "3-1") (pinfunction "5V_3-1") (pintype "bidirectional"))
      (node (ref "U$35") (pin "P$8") (pinfunction "VCC_P$8") (pintype "bidirectional"))
      (node (ref "U$39") (pin "P$8") (pinfunction "VCC_P$8") (pintype "bidirectional"))
      (node (ref "U$4") (pin "P$8") (pinfunction "VCC_P$8") (pintype "bidirectional"))
      (node (ref "U$45") (pin "P$5") (pinfunction "VDD_P$5") (pintype "bidirectional"))
      (node (ref "U$8") (pin "P$8") (pinfunction "VCC_P$8") (pintype "bidirectional"))
      (node (ref "U1") (pin "1") (pinfunction "A0_1") (pintype "bidirectional"))
      (node (ref "U1") (pin "2") (pinfunction "A1_2") (pintype "bidirectional"))
      (node (ref "U1") (pin "24") (pinfunction "A5_24") (pintype "bidirectional"))
      (node (ref "U1") (pin "28") (pinfunction "VDD_28") (pintype "bidirectional"))
      (node (ref "U1") (pin "3") (pinfunction "A2_3") (pintype "bidirectional"))
      (node (ref "U1") (pin "4") (pinfunction "A3_4") (pintype "bidirectional"))
      (node (ref "U1") (pin "5") (pinfunction "A4_5") (pintype "bidirectional"))
      (node (ref "V-THRUST_CURR_ADC") (pin "P$3") (pinfunction "ADR0_P$3") (pintype "bidirectional"))
      (node (ref "V-THRUST_CURR_ADC") (pin "P$5") (pinfunction "VDD_P$5") (pintype "bidirectional"))
      (node (ref "V-THRUST_CURR_ADC") (pin "P$6") (pinfunction "ADR1_P$6") (pintype "bidirectional"))
      (node (ref "V-THRUST_VOLTAGE") (pin "P$4") (pinfunction "VS_P$4") (pintype "bidirectional"))
      (node (ref "V-THRUST_VOLTAGE") (pin "P$7") (pinfunction "A0_P$7") (pintype "bidirectional"))
      (node (ref "V-THRUST_VOLTAGE") (pin "P$8") (pinfunction "A1_P$8") (pintype "bidirectional"))
    )
    (net (code "4") (name "/AIN0") (class "Default")
      (node (ref "U$3") (pin "3-9") (pinfunction "PE3_3-9") (pintype "bidirectional"))
    )
    (net (code "5") (name "/AIN1") (class "Default")
      (node (ref "U$3") (pin "3-8") (pinfunction "PE2_3-8") (pintype "bidirectional"))
    )
    (net (code "6") (name "/AIN2") (class "Default")
      (node (ref "U$3") (pin "3-7") (pinfunction "PE1_3-7") (pintype "bidirectional"))
    )
    (net (code "7") (name "/AIN3") (class "Default")
      (node (ref "U$3") (pin "2-3") (pinfunction "PE0_2-3") (pintype "bidirectional"))
    )
    (net (code "8") (name "/AIN4") (class "Default")
      (node (ref "U$3") (pin "3-6") (pinfunction "PD3_3-6") (pintype "bidirectional"))
    )
    (net (code "9") (name "/AIN5") (class "Default")
      (node (ref "U$3") (pin "3-5") (pinfunction "PD2_3-5") (pintype "bidirectional"))
    )
    (net (code "10") (name "/AIN8") (class "Default")
      (node (ref "U$3") (pin "1-6") (pinfunction "PE5_1-6") (pintype "bidirectional"))
    )
    (net (code "11") (name "/AIN9") (class "Default")
      (node (ref "U$3") (pin "1-5") (pinfunction "PE4_1-5") (pintype "bidirectional"))
    )
    (net (code "12") (name "/AIN10") (class "Default")
      (node (ref "U$3") (pin "1-7") (pinfunction "PB4_1-7") (pintype "bidirectional"))
    )
    (net (code "13") (name "/AIN11") (class "Default")
      (node (ref "U$3") (pin "1-2") (pinfunction "PB5_1-2") (pintype "bidirectional"))
    )
    (net (code "14") (name "/CPU_ON") (class "Default")
      (node (ref "12V_REG") (pin "14") (pinfunction "EN/UV_14") (pintype "bidirectional"))
      (node (ref "JP1") (pin "2") (pinfunction "2_2") (pintype "passive"))
      (node (ref "U$45") (pin "P$4") (pinfunction "OUT_P$4") (pintype "bidirectional"))
    )
    (net (code "15") (name "/GND") (class "Default")
      (node (ref "12V_CURR_ADC") (pin "P$3") (pinfunction "ADR0_P$3") (pintype "bidirectional"))
      (node (ref "12V_CURR_ADC") (pin "P$6") (pinfunction "ADR1_P$6") (pintype "bidirectional"))
      (node (ref "12V_CURR_ADC") (pin "P$7") (pinfunction "GND_P$7") (pintype "bidirectional"))
      (node (ref "12V_LED") (pin "P$2") (pinfunction "C_P$2") (pintype "passive"))
      (node (ref "12V_OUT") (pin "P$2") (pinfunction "P$2_P$2") (pintype "bidirectional"))
      (node (ref "12V_REG") (pin "10") (pinfunction "GND-2_10") (pintype "bidirectional"))
      (node (ref "12V_REG") (pin "11") (pinfunction "GND-2_11") (pintype "bidirectional"))
      (node (ref "12V_REG") (pin "18") (pinfunction "GND_18") (pintype "bidirectional"))
      (node (ref "12V_REG") (pin "6") (pinfunction "GND-1_6") (pintype "bidirectional"))
      (node (ref "12V_REG") (pin "7") (pinfunction "GND-1_7") (pintype "bidirectional"))
      (node (ref "12V_VOLTAGE") (pin "P$3") (pinfunction "GND_P$3") (pintype "bidirectional"))
      (node (ref "12V_VOLTAGE") (pin "P$7") (pinfunction "A0_P$7") (pintype "bidirectional"))
      (node (ref "3V3_LED") (pin "P$2") (pinfunction "C_P$2") (pintype "passive"))
      (node (ref "5-TVS_1") (pin "P$2") (pinfunction "P$2_P$2") (pintype "bidirectional"))
      (node (ref "5-TVS_1") (pin "P$5") (pinfunction "P$5_P$5") (pintype "bidirectional"))
      (node (ref "5-TVS_2") (pin "P$2") (pinfunction "P$2_P$2") (pintype "bidirectional"))
      (node (ref "5-TVS_2") (pin "P$5") (pinfunction "P$5_P$5") (pintype "bidirectional"))
      (node (ref "5V_CURR_ADC") (pin "P$3") (pinfunction "ADR0_P$3") (pintype "bidirectional"))
      (node (ref "5V_CURR_ADC") (pin "P$7") (pinfunction "GND_P$7") (pintype "bidirectional"))
      (node (ref "5V_LED") (pin "P$2") (pinfunction "C_P$2") (pintype "passive"))
      (node (ref "5V_OUT") (pin "P$2") (pinfunction "P$2_P$2") (pintype "bidirectional"))
      (node (ref "5V_PG") (pin "C") (pinfunction "C_C") (pintype "passive"))
      (node (ref "5V_REG") (pin "10") (pinfunction "GND-2_10") (pintype "bidirectional"))
      (node (ref "5V_REG") (pin "11") (pinfunction "GND-2_11") (pintype "bidirectional"))
      (node (ref "5V_REG") (pin "18") (pinfunction "GND_18") (pintype "bidirectional"))
      (node (ref "5V_REG") (pin "6") (pinfunction "GND-1_6") (pintype "bidirectional"))
      (node (ref "5V_REG") (pin "7") (pinfunction "GND-1_7") (pintype "bidirectional"))
      (node (ref "5V_VOLTAGE") (pin "P$3") (pinfunction "GND_P$3") (pintype "bidirectional"))
      (node (ref "5V_VOLTAGE") (pin "P$7") (pinfunction "A0_P$7") (pintype "bidirectional"))
      (node (ref "5V_VOLTAGE") (pin "P$8") (pinfunction "A1_P$8") (pintype "bidirectional"))
      (node (ref "BME280") (pin "P$1") (pinfunction "GND1_P$1") (pintype "bidirectional"))
      (node (ref "BME280") (pin "P$7") (pinfunction "GND2_P$7") (pintype "bidirectional"))
      (node (ref "C1") (pin "2") (pinfunction "2_2") (pintype "passive"))
      (node (ref "C10") (pin "2") (pinfunction "2_2") (pintype "passive"))
      (node (ref "C100") (pin "2") (pinfunction "2_2") (pintype "passive"))
      (node (ref "C11") (pin "2") (pinfunction "2_2") (pintype "passive"))
      (node (ref "C12") (pin "2") (pinfunction "2_2") (pintype "passive"))
      (node (ref "C13") (pin "2") (pinfunction "2_2") (pintype "passive"))
      (node (ref "C14") (pin "2") (pinfunction "2_2") (pintype "passive"))
      (node (ref "C15") (pin "2") (pinfunction "2_2") (pintype "passive"))
      (node (ref "C16") (pin "2") (pinfunction "2_2") (pintype "passive"))
      (node (ref "C17") (pin "2") (pinfunction "2_2") (pintype "passive"))
      (node (ref "C18") (pin "2") (pinfunction "2_2") (pintype "passive"))
      (node (ref "C19") (pin "2") (pinfunction "2_2") (pintype "passive"))
      (node (ref "C2") (pin "2") (pinfunction "2_2") (pintype "passive"))
      (node (ref "C20") (pin "2") (pinfunction "2_2") (pintype "passive"))
      (node (ref "C21") (pin "2") (pinfunction "2_2") (pintype "passive"))
      (node (ref "C22") (pin "2") (pinfunction "2_2") (pintype "passive"))
      (node (ref "C23") (pin "2") (pinfunction "2_2") (pintype "passive"))
      (node (ref "C24") (pin "2") (pinfunction "2_2") (pintype "passive"))
      (node (ref "C25") (pin "2") (pinfunction "2_2") (pintype "passive"))
      (node (ref "C26") (pin "2") (pinfunction "2_2") (pintype "passive"))
      (node (ref "C27") (pin "2") (pinfunction "2_2") (pintype "passive"))
      (node (ref "C29") (pin "2") (pinfunction "2_2") (pintype "passive"))
      (node (ref "C3") (pin "2") (pinfunction "2_2") (pintype "passive"))
      (node (ref "C30") (pin "2") (pinfunction "2_2") (pintype "passive"))
      (node (ref "C31") (pin "2") (pinfunction "2_2") (pintype "passive"))
      (node (ref "C32") (pin "2") (pinfunction "2_2") (pintype "passive"))
      (node (ref "C33") (pin "2") (pinfunction "2_2") (pintype "passive"))
      (node (ref "C34") (pin "2") (pinfunction "2_2") (pintype "passive"))
      (node (ref "C35") (pin "2") (pinfunction "2_2") (pintype "passive"))
      (node (ref "C36") (pin "P$2") (pinfunction "-_P$2") (pintype "passive"))
      (node (ref "C37") (pin "2") (pinfunction "2_2") (pintype "passive"))
      (node (ref "C38") (pin "2") (pinfunction "2_2") (pintype "passive"))
      (node (ref "C39") (pin "2") (pinfunction "2_2") (pintype "passive"))
      (node (ref "C4") (pin "2") (pinfunction "2_2") (pintype "passive"))
      (node (ref "C40") (pin "2") (pinfunction "2_2") (pintype "passive"))
      (node (ref "C43") (pin "2") (pinfunction "2_2") (pintype "passive"))
      (node (ref "C44") (pin "2") (pinfunction "2_2") (pintype "passive"))
      (node (ref "C45") (pin "2") (pinfunction "2_2") (pintype "passive"))
      (node (ref "C46") (pin "2") (pinfunction "2_2") (pintype "passive"))
      (node (ref "C47") (pin "2") (pinfunction "2_2") (pintype "passive"))
      (node (ref "C48") (pin "2") (pinfunction "2_2") (pintype "passive"))
      (node (ref "C49") (pin "2") (pinfunction "2_2") (pintype "passive"))
      (node (ref "C5") (pin "2") (pinfunction "2_2") (pintype "passive"))
      (node (ref "C50") (pin "2") (pinfunction "2_2") (pintype "passive"))
      (node (ref "C51") (pin "2") (pinfunction "2_2") (pintype "passive"))
      (node (ref "C52") (pin "2") (pinfunction "2_2") (pintype "passive"))
      (node (ref "C53") (pin "2") (pinfunction "2_2") (pintype "passive"))
      (node (ref "C54") (pin "2") (pinfunction "2_2") (pintype "passive"))
      (node (ref "C55") (pin "2") (pinfunction "2_2") (pintype "passive"))
      (node (ref "C56") (pin "2") (pinfunction "2_2") (pintype "passive"))
      (node (ref "C57") (pin "2") (pinfunction "2_2") (pintype "passive"))
      (node (ref "C58") (pin "2") (pinfunction "2_2") (pintype "passive"))
      (node (ref "C6") (pin "2") (pinfunction "2_2") (pintype "passive"))
      (node (ref "C60") (pin "2") (pinfunction "2_2") (pintype "passive"))
      (node (ref "C61") (pin "2") (pinfunction "2_2") (pintype "passive"))
      (node (ref "C62") (pin "P$2") (pinfunction "-_P$2") (pintype "passive"))
      (node (ref "C63") (pin "2") (pinfunction "2_2") (pintype "passive"))
      (node (ref "C67") (pin "2") (pinfunction "2_2") (pintype "passive"))
      (node (ref "C68") (pin "2") (pinfunction "2_2") (pintype "passive"))
      (node (ref "C7") (pin "2") (pinfunction "2_2") (pintype "passive"))
      (node (ref "C77") (pin "2") (pinfunction "2_2") (pintype "passive"))
      (node (ref "C78") (pin "2") (pinfunction "2_2") (pintype "passive"))
      (node (ref "C8") (pin "2") (pinfunction "2_2") (pintype "passive"))
      (node (ref "C81") (pin "2") (pinfunction "2_2") (pintype "passive"))
      (node (ref "C82") (pin "2") (pinfunction "2_2") (pintype "passive"))
      (node (ref "C83") (pin "2") (pinfunction "2_2") (pintype "passive"))
      (node (ref "C84") (pin "2") (pinfunction "2_2") (pintype "passive"))
      (node (ref "C85") (pin "2") (pinfunction "2_2") (pintype "passive"))
      (node (ref "C86") (pin "2") (pinfunction "2_2") (pintype "passive"))
      (node (ref "C87") (pin "2") (pinfunction "2_2") (pintype "passive"))
      (node (ref "C88") (pin "2") (pinfunction "2_2") (pintype "passive"))
      (node (ref "C89") (pin "2") (pinfunction "2_2") (pintype "passive"))
      (node (ref "C9") (pin "2") (pinfunction "2_2") (pintype "passive"))
      (node (ref "C90") (pin "2") (pinfunction "2_2") (pintype "passive"))
      (node (ref "C91") (pin "2") (pinfunction "2_2") (pintype "passive"))
      (node (ref "C92") (pin "2") (pinfunction "2_2") (pintype "passive"))
      (node (ref "C93") (pin "2") (pinfunction "2_2") (pintype "passive"))
      (node (ref "C95") (pin "2") (pinfunction "2_2") (pintype "passive"))
      (node (ref "C96") (pin "2") (pinfunction "2_2") (pintype "passive"))
      (node (ref "C97") (pin "2") (pinfunction "2_2") (pintype "passive"))
      (node (ref "C98") (pin "2") (pinfunction "2_2") (pintype "passive"))
      (node (ref "C99") (pin "2") (pinfunction "2_2") (pintype "passive"))
      (node (ref "CAMERA1") (pin "P$2") (pinfunction "P$2_P$2") (pintype "bidirectional"))
      (node (ref "CAMERA2") (pin "P$2") (pinfunction "P$2_P$2") (pintype "bidirectional"))
      (node (ref "CPU_ON") (pin "P$2") (pinfunction "P$2_P$2") (pintype "bidirectional"))
      (node (ref "CPU_PWR") (pin "P$1") (pinfunction "P$1_P$1") (pintype "bidirectional"))
      (node (ref "CPU_PWR") (pin "P$2") (pinfunction "P$2_P$2") (pintype "bidirectional"))
      (node (ref "DEPTH_SENS") (pin "P$3") (pinfunction "P$3_P$3") (pintype "bidirectional"))
      (node (ref "ETHERNET") (pin "P$2") (pinfunction "P$2_P$2") (pintype "bidirectional"))
      (node (ref "FAN1") (pin "P$2") (pinfunction "P$2_P$2") (pintype "bidirectional"))
      (node (ref "FAN2") (pin "P$2") (pinfunction "P$2_P$2") (pintype "bidirectional"))
      (node (ref "I2C_SHIFT") (pin "P$1") (pinfunction "GND_P$1") (pintype "bidirectional"))
      (node (ref "JP2") (pin "P$1") (pinfunction "P$1_P$1") (pintype "bidirectional"))
      (node (ref "LED2") (pin "C") (pinfunction "C_C") (pintype "passive"))
      (node (ref "R14") (pin "1") (pinfunction "1_1") (pintype "passive"))
      (node (ref "R16") (pin "1") (pinfunction "1_1") (pintype "passive"))
      (node (ref "R17") (pin "1") (pinfunction "1_1") (pintype "passive"))
      (node (ref "R24") (pin "1") (pinfunction "1_1") (pintype "passive"))
      (node (ref "THRUST1") (pin "P$1") (pinfunction "P$1_P$1") (pintype "bidirectional"))
      (node (ref "THRUST1") (pin "P$3") (pinfunction "P$3_P$3") (pintype "bidirectional"))
      (node (ref "THRUST2") (pin "P$1") (pinfunction "P$1_P$1") (pintype "bidirectional"))
      (node (ref "THRUST2") (pin "P$3") (pinfunction "P$3_P$3") (pintype "bidirectional"))
      (node (ref "THRUST3") (pin "P$1") (pinfunction "P$1_P$1") (pintype "bidirectional"))
      (node (ref "THRUST3") (pin "P$3") (pinfunction "P$3_P$3") (pintype "bidirectional"))
      (node (ref "THRUST4") (pin "P$1") (pinfunction "P$1_P$1") (pintype "bidirectional"))
      (node (ref "THRUST4") (pin "P$3") (pinfunction "P$3_P$3") (pintype "bidirectional"))
      (node (ref "THRUST5") (pin "P$1") (pinfunction "P$1_P$1") (pintype "bidirectional"))
      (node (ref "THRUST5") (pin "P$3") (pinfunction "P$3_P$3") (pintype "bidirectional"))
      (node (ref "THRUST6") (pin "P$1") (pinfunction "P$1_P$1") (pintype "bidirectional"))
      (node (ref "THRUST6") (pin "P$3") (pinfunction "P$3_P$3") (pintype "bidirectional"))
      (node (ref "THRUST7") (pin "P$1") (pinfunction "P$1_P$1") (pintype "bidirectional"))
      (node (ref "THRUST7") (pin "P$3") (pinfunction "P$3_P$3") (pintype "bidirectional"))
      (node (ref "THRUST8") (pin "P$1") (pinfunction "P$1_P$1") (pintype "bidirectional"))
      (node (ref "THRUST8") (pin "P$3") (pinfunction "P$3_P$3") (pintype "bidirectional"))
      (node (ref "THRUSTER_CURR_ADC") (pin "11") (pinfunction "COM_11") (pintype "bidirectional"))
      (node (ref "THRUSTER_CURR_ADC") (pin "12") (pinfunction "A0_12") (pintype "bidirectional"))
      (node (ref "THRUSTER_CURR_ADC") (pin "13") (pinfunction "A1_13") (pintype "bidirectional"))
      (node (ref "THRUSTER_CURR_ADC") (pin "9") (pinfunction "GND_9") (pintype "bidirectional"))
      (node (ref "TVS1") (pin "P$2") (pinfunction "P$2_P$2") (pintype "bidirectional"))
      (node (ref "TVS2") (pin "P$2") (pinfunction "P$2_P$2") (pintype "bidirectional"))
      (node (ref "TVS3") (pin "P$2") (pinfunction "P$2_P$2") (pintype "bidirectional"))
      (node (ref "U$10") (pin "P$1") (pinfunction "A_P$1") (pintype "passive"))
      (node (ref "U$11") (pin "P$5") (pinfunction "GND_P$5") (pintype "bidirectional"))
      (node (ref "U$13") (pin "P$1") (pinfunction "A_P$1") (pintype "passive"))
      (node (ref "U$14") (pin "P$5") (pinfunction "GND_P$5") (pintype "bidirectional"))
      (node (ref "U$16") (pin "P$1") (pinfunction "A_P$1") (pintype "passive"))
      (node (ref "U$17") (pin "P$5") (pinfunction "GND_P$5") (pintype "bidirectional"))
      (node (ref "U$19") (pin "P$5") (pinfunction "GND_P$5") (pintype "bidirectional"))
      (node (ref "U$2") (pin "P$5") (pinfunction "GND_P$5") (pintype "bidirectional"))
      (node (ref "U$22") (pin "P$1") (pinfunction "A_P$1") (pintype "passive"))
      (node (ref "U$23") (pin "P$5") (pinfunction "GND_P$5") (pintype "bidirectional"))
      (node (ref "U$26") (pin "P$1") (pinfunction "A_P$1") (pintype "passive"))
      (node (ref "U$28") (pin "P$1") (pinfunction "A_P$1") (pintype "passive"))
      (node (ref "U$29") (pin "P$5") (pinfunction "GND_P$5") (pintype "bidirectional"))
      (node (ref "U$3") (pin "2-1") (pinfunction "GND_2-1") (pintype "bidirectional"))
      (node (ref "U$3") (pin "3-2") (pinfunction "GND_3-2") (pintype "bidirectional"))
      (node (ref "U$30") (pin "P$1") (pinfunction "A_P$1") (pintype "passive"))
      (node (ref "U$31") (pin "P$1") (pinfunction "A_P$1") (pintype "passive"))
      (node (ref "U$32") (pin "P$1") (pinfunction "A_P$1") (pintype "passive"))
      (node (ref "U$33") (pin "P$1") (pinfunction "A_P$1") (pintype "passive"))
      (node (ref "U$34") (pin "P$1") (pinfunction "A_P$1") (pintype "passive"))
      (node (ref "U$35") (pin "P$5") (pinfunction "GND_P$5") (pintype "bidirectional"))
      (node (ref "U$38") (pin "P$1") (pinfunction "A_P$1") (pintype "passive"))
      (node (ref "U$39") (pin "P$5") (pinfunction "GND_P$5") (pintype "bidirectional"))
      (node (ref "U$4") (pin "P$5") (pinfunction "GND_P$5") (pintype "bidirectional"))
      (node (ref "U$45") (pin "P$3") (pinfunction "GND_P$3") (pintype "bidirectional"))
      (node (ref "U$59") (pin "P$1") (pinfunction "A_P$1") (pintype "passive"))
      (node (ref "U$7") (pin "P$1") (pinfunction "A_P$1") (pintype "passive"))
      (node (ref "U$8") (pin "P$5") (pinfunction "GND_P$5") (pintype "bidirectional"))
      (node (ref "U1") (pin "14") (pinfunction "VSS_14") (pintype "bidirectional"))
      (node (ref "U1") (pin "23") (pinfunction "~{OE}_23") (pintype "bidirectional"))
      (node (ref "U1") (pin "25") (pinfunction "EXTCLK_25") (pintype "bidirectional"))
      (node (ref "V-THRUST_CURR_ADC") (pin "P$7") (pinfunction "GND_P$7") (pintype "bidirectional"))
      (node (ref "V-THRUST_LED") (pin "P$2") (pinfunction "C_P$2") (pintype "passive"))
      (node (ref "V-THRUST_OUT") (pin "P$2") (pinfunction "P$2_P$2") (pintype "bidirectional"))
      (node (ref "V-THRUST_VOLTAGE") (pin "P$3") (pinfunction "GND_P$3") (pintype "bidirectional"))
    )
    (net (code "16") (name "/RELAY_OUT") (class "Default")
      (node (ref "12V_REG") (pin "13") (pinfunction "VIN-2_13") (pintype "bidirectional"))
      (node (ref "12V_REG") (pin "4") (pinfunction "VIN-1_4") (pintype "bidirectional"))
      (node (ref "5V_REG") (pin "13") (pinfunction "VIN-2_13") (pintype "bidirectional"))
      (node (ref "5V_REG") (pin "14") (pinfunction "EN/UV_14") (pintype "bidirectional"))
      (node (ref "5V_REG") (pin "4") (pinfunction "VIN-1_4") (pintype "bidirectional"))
      (node (ref "C27") (pin "1") (pinfunction "1_1") (pintype "passive"))
      (node (ref "C34") (pin "1") (pinfunction "1_1") (pintype "passive"))
      (node (ref "C38") (pin "1") (pinfunction "1_1") (pintype "passive"))
      (node (ref "C4") (pin "1") (pinfunction "1_1") (pintype "passive"))
      (node (ref "C40") (pin "1") (pinfunction "1_1") (pintype "passive"))
      (node (ref "C60") (pin "1") (pinfunction "1_1") (pintype "passive"))
      (node (ref "JP1") (pin "1") (pinfunction "1_1") (pintype "passive"))
      (node (ref "JP2") (pin "P$2") (pinfunction "P$2_P$2") (pintype "bidirectional"))
      (node (ref "R3") (pin "2") (pinfunction "2_2") (pintype "passive"))
      (node (ref "R40") (pin "2") (pinfunction "2_2") (pintype "passive"))
      (node (ref "U$1") (pin "P$3") (pinfunction "S_P$3") (pintype "bidirectional"))
      (node (ref "U$19") (pin "P$1") (pinfunction "IP+_P$1") (pintype "bidirectional"))
      (node (ref "U$19") (pin "P$2") (pinfunction "IP+_P$2") (pintype "bidirectional"))
      (node (ref "U$66") (pin "P$3") (pinfunction "S_P$3") (pintype "bidirectional"))
      (node (ref "U$7") (pin "P$2") (pinfunction "C_P$2") (pintype "passive"))
    )
    (net (code "17") (name "/RX") (class "Default")
      (node (ref "U$3") (pin "1-3") (pinfunction "PB0_1-3") (pintype "bidirectional"))
    )
    (net (code "18") (name "/SCL-3V3") (class "Default")
      (node (ref "BME280") (pin "P$4") (pinfunction "SCK/SCL_P$4") (pintype "bidirectional"))
      (node (ref "DEPTH_SENS") (pin "P$1") (pinfunction "P$1_P$1") (pintype "bidirectional"))
      (node (ref "I2C_SHIFT") (pin "P$3") (pinfunction "SCL1_P$3") (pintype "bidirectional"))
      (node (ref "R11") (pin "1") (pinfunction "1_1") (pintype "passive"))
    )
    (net (code "19") (name "/SCL1") (class "Default")
      (node (ref "12V_CURR_ADC") (pin "P$1") (pinfunction "SCL_P$1") (pintype "bidirectional"))
      (node (ref "12V_VOLTAGE") (pin "P$5") (pinfunction "SCL_P$5") (pintype "bidirectional"))
      (node (ref "5V_CURR_ADC") (pin "P$1") (pinfunction "SCL_P$1") (pintype "bidirectional"))
      (node (ref "5V_VOLTAGE") (pin "P$5") (pinfunction "SCL_P$5") (pintype "bidirectional"))
      (node (ref "I2C_SHIFT") (pin "P$6") (pinfunction "SCL2_P$6") (pintype "bidirectional"))
      (node (ref "R8") (pin "1") (pinfunction "1_1") (pintype "passive"))
      (node (ref "THRUSTER_CURR_ADC") (pin "14") (pinfunction "SCL_14") (pintype "bidirectional"))
      (node (ref "U$3") (pin "1-9") (pinfunction "PA6_1-9") (pintype "bidirectional"))
      (node (ref "U1") (pin "26") (pinfunction "SCL_26") (pintype "bidirectional"))
      (node (ref "V-THRUST_CURR_ADC") (pin "P$1") (pinfunction "SCL_P$1") (pintype "bidirectional"))
      (node (ref "V-THRUST_VOLTAGE") (pin "P$5") (pinfunction "SCL_P$5") (pintype "bidirectional"))
    )
    (net (code "20") (name "/SCL3") (class "Default")
      (node (ref "U$3") (pin "2-7") (pinfunction "PD0_2-7") (pintype "bidirectional"))
    )
    (net (code "21") (name "/SDA-3V3") (class "Default")
      (node (ref "BME280") (pin "P$3") (pinfunction "SDI/SDA_P$3") (pintype "bidirectional"))
      (node (ref "DEPTH_SENS") (pin "P$2") (pinfunction "P$2_P$2") (pintype "bidirectional"))
      (node (ref "I2C_SHIFT") (pin "P$4") (pinfunction "SDA1_P$4") (pintype "bidirectional"))
      (node (ref "R10") (pin "1") (pinfunction "1_1") (pintype "passive"))
    )
    (net (code "22") (name "/SDA1") (class "Default")
      (node (ref "12V_CURR_ADC") (pin "P$8") (pinfunction "SDA_P$8") (pintype "bidirectional"))
      (node (ref "12V_VOLTAGE") (pin "P$6") (pinfunction "SDA_P$6") (pintype "bidirectional"))
      (node (ref "5V_CURR_ADC") (pin "P$8") (pinfunction "SDA_P$8") (pintype "bidirectional"))
      (node (ref "5V_VOLTAGE") (pin "P$6") (pinfunction "SDA_P$6") (pintype "bidirectional"))
      (node (ref "I2C_SHIFT") (pin "P$5") (pinfunction "SDA2_P$5") (pintype "bidirectional"))
      (node (ref "R7") (pin "1") (pinfunction "1_1") (pintype "passive"))
      (node (ref "THRUSTER_CURR_ADC") (pin "15") (pinfunction "SDA_15") (pintype "bidirectional"))
      (node (ref "U$3") (pin "1-10") (pinfunction "PA7_1-10") (pintype "bidirectional"))
      (node (ref "U1") (pin "27") (pinfunction "SDA_27") (pintype "bidirectional"))
      (node (ref "V-THRUST_CURR_ADC") (pin "P$8") (pinfunction "SDA_P$8") (pintype "bidirectional"))
      (node (ref "V-THRUST_VOLTAGE") (pin "P$6") (pinfunction "SDA_P$6") (pintype "bidirectional"))
    )
    (net (code "23") (name "/SDA3") (class "Default")
      (node (ref "U$3") (pin "2-6") (pinfunction "PD1_2-6") (pintype "bidirectional"))
    )
    (net (code "24") (name "/T1_CURR") (class "Default")
      (node (ref "THRUSTER_CURR_ADC") (pin "1") (pinfunction "CH0_1") (pintype "bidirectional"))
      (node (ref "U$4") (pin "P$7") (pinfunction "VIOUT_P$7") (pintype "bidirectional"))
    )
    (net (code "25") (name "/T1_PWM") (class "Default")
      (node (ref "THRUST1") (pin "P$2") (pinfunction "P$2_P$2") (pintype "bidirectional"))
      (node (ref "U1") (pin "6") (pinfunction "CH0_6") (pintype "bidirectional"))
    )
    (net (code "26") (name "/T2_CURR") (class "Default")
      (node (ref "THRUSTER_CURR_ADC") (pin "2") (pinfunction "CH1_2") (pintype "bidirectional"))
      (node (ref "U$8") (pin "P$7") (pinfunction "VIOUT_P$7") (pintype "bidirectional"))
    )
    (net (code "27") (name "/T2_PWM") (class "Default")
      (node (ref "THRUST2") (pin "P$2") (pinfunction "P$2_P$2") (pintype "bidirectional"))
      (node (ref "U1") (pin "7") (pinfunction "CH1_7") (pintype "bidirectional"))
    )
    (net (code "28") (name "/T3_CURR") (class "Default")
      (node (ref "THRUSTER_CURR_ADC") (pin "3") (pinfunction "CH2_3") (pintype "bidirectional"))
      (node (ref "U$11") (pin "P$7") (pinfunction "VIOUT_P$7") (pintype "bidirectional"))
    )
    (net (code "29") (name "/T3_PWM") (class "Default")
      (node (ref "THRUST3") (pin "P$2") (pinfunction "P$2_P$2") (pintype "bidirectional"))
      (node (ref "U1") (pin "8") (pinfunction "CH2_8") (pintype "bidirectional"))
    )
    (net (code "30") (name "/T4_CURR") (class "Default")
      (node (ref "THRUSTER_CURR_ADC") (pin "4") (pinfunction "CH3_4") (pintype "bidirectional"))
      (node (ref "U$14") (pin "P$7") (pinfunction "VIOUT_P$7") (pintype "bidirectional"))
    )
    (net (code "31") (name "/T4_PWM") (class "Default")
      (node (ref "THRUST4") (pin "P$2") (pinfunction "P$2_P$2") (pintype "bidirectional"))
      (node (ref "U1") (pin "9") (pinfunction "CH3_9") (pintype "bidirectional"))
    )
    (net (code "32") (name "/T5_CURR") (class "Default")
      (node (ref "THRUSTER_CURR_ADC") (pin "5") (pinfunction "CH4_5") (pintype "bidirectional"))
      (node (ref "U$17") (pin "P$7") (pinfunction "VIOUT_P$7") (pintype "bidirectional"))
    )
    (net (code "33") (name "/T5_PWM") (class "Default")
      (node (ref "THRUST5") (pin "P$2") (pinfunction "P$2_P$2") (pintype "bidirectional"))
      (node (ref "U1") (pin "10") (pinfunction "CH4_10") (pintype "bidirectional"))
    )
    (net (code "34") (name "/T6_CURR") (class "Default")
      (node (ref "THRUSTER_CURR_ADC") (pin "6") (pinfunction "CH5_6") (pintype "bidirectional"))
      (node (ref "U$23") (pin "P$7") (pinfunction "VIOUT_P$7") (pintype "bidirectional"))
    )
    (net (code "35") (name "/T6_PWM") (class "Default")
      (node (ref "THRUST6") (pin "P$2") (pinfunction "P$2_P$2") (pintype "bidirectional"))
      (node (ref "U1") (pin "11") (pinfunction "CH5_11") (pintype "bidirectional"))
    )
    (net (code "36") (name "/T7_CURR") (class "Default")
      (node (ref "THRUSTER_CURR_ADC") (pin "7") (pinfunction "CH6_7") (pintype "bidirectional"))
      (node (ref "U$29") (pin "P$7") (pinfunction "VIOUT_P$7") (pintype "bidirectional"))
    )
    (net (code "37") (name "/T7_PWM") (class "Default")
      (node (ref "THRUST7") (pin "P$2") (pinfunction "P$2_P$2") (pintype "bidirectional"))
      (node (ref "U1") (pin "12") (pinfunction "CH6_12") (pintype "bidirectional"))
    )
    (net (code "38") (name "/T8_CURR") (class "Default")
      (node (ref "THRUSTER_CURR_ADC") (pin "8") (pinfunction "CH7_8") (pintype "bidirectional"))
      (node (ref "U$39") (pin "P$7") (pinfunction "VIOUT_P$7") (pintype "bidirectional"))
    )
    (net (code "39") (name "/T8_PWM") (class "Default")
      (node (ref "THRUST8") (pin "P$2") (pinfunction "P$2_P$2") (pintype "bidirectional"))
      (node (ref "U1") (pin "13") (pinfunction "CH7_13") (pintype "bidirectional"))
    )
    (net (code "40") (name "/TX") (class "Default")
      (node (ref "U$3") (pin "1-4") (pinfunction "PB1_1-4") (pintype "bidirectional"))
    )
    (net (code "41") (name "/V_THRUST") (class "Default")
      (node (ref "C46") (pin "1") (pinfunction "1_1") (pintype "passive"))
      (node (ref "C47") (pin "1") (pinfunction "1_1") (pintype "passive"))
      (node (ref "C49") (pin "1") (pinfunction "1_1") (pintype "passive"))
      (node (ref "CAMERA1") (pin "P$1") (pinfunction "P$1_P$1") (pintype "bidirectional"))
      (node (ref "CAMERA2") (pin "P$1") (pinfunction "P$1_P$1") (pintype "bidirectional"))
      (node (ref "R30") (pin "1") (pinfunction "1_1") (pintype "passive"))
      (node (ref "R32") (pin "2") (pinfunction "2_2") (pintype "passive"))
      (node (ref "U$11") (pin "P$1") (pinfunction "IP+_P$1") (pintype "bidirectional"))
      (node (ref "U$11") (pin "P$2") (pinfunction "IP+_P$2") (pintype "bidirectional"))
      (node (ref "U$14") (pin "P$1") (pinfunction "IP+_P$1") (pintype "bidirectional"))
      (node (ref "U$14") (pin "P$2") (pinfunction "IP+_P$2") (pintype "bidirectional"))
      (node (ref "U$17") (pin "P$1") (pinfunction "IP+_P$1") (pintype "bidirectional"))
      (node (ref "U$17") (pin "P$2") (pinfunction "IP+_P$2") (pintype "bidirectional"))
      (node (ref "U$23") (pin "P$1") (pinfunction "IP+_P$1") (pintype "bidirectional"))
      (node (ref "U$23") (pin "P$2") (pinfunction "IP+_P$2") (pintype "bidirectional"))
      (node (ref "U$29") (pin "P$1") (pinfunction "IP+_P$1") (pintype "bidirectional"))
      (node (ref "U$29") (pin "P$2") (pinfunction "IP+_P$2") (pintype "bidirectional"))
      (node (ref "U$32") (pin "P$2") (pinfunction "C_P$2") (pintype "passive"))
      (node (ref "U$33") (pin "P$2") (pinfunction "C_P$2") (pintype "passive"))
      (node (ref "U$34") (pin "P$2") (pinfunction "C_P$2") (pintype "passive"))
      (node (ref "U$38") (pin "P$2") (pinfunction "C_P$2") (pintype "passive"))
      (node (ref "U$39") (pin "P$1") (pinfunction "IP+_P$1") (pintype "bidirectional"))
      (node (ref "U$39") (pin "P$2") (pinfunction "IP+_P$2") (pintype "bidirectional"))
      (node (ref "U$4") (pin "P$1") (pinfunction "IP+_P$1") (pintype "bidirectional"))
      (node (ref "U$4") (pin "P$2") (pinfunction "IP+_P$2") (pintype "bidirectional"))
      (node (ref "U$5") (pin "P$3") (pinfunction "P$2_P$3") (pintype "bidirectional"))
      (node (ref "U$5") (pin "P$4") (pinfunction "P$2_P$4") (pintype "bidirectional"))
      (node (ref "U$8") (pin "P$1") (pinfunction "IP+_P$1") (pintype "bidirectional"))
      (node (ref "U$8") (pin "P$2") (pinfunction "IP+_P$2") (pintype "bidirectional"))
      (node (ref "V-THRUST_OUT") (pin "P$1") (pinfunction "P$1_P$1") (pintype "bidirectional"))
    )
    (net (code "42") (name "Net-(3V3_LED-A)") (class "Default")
      (node (ref "3V3_LED") (pin "P$1") (pinfunction "A_P$1") (pintype "passive"))
      (node (ref "R34") (pin "1") (pinfunction "1_1") (pintype "passive"))
    )
    (net (code "43") (name "Net-(5V_CURR_ADC-VIN)") (class "Default")
      (node (ref "5V_CURR_ADC") (pin "P$4") (pinfunction "VIN_P$4") (pintype "bidirectional"))
      (node (ref "U$2") (pin "P$7") (pinfunction "VIOUT_P$7") (pintype "bidirectional"))
    )
    (net (code "44") (name "Net-(5V_LED-A)") (class "Default")
      (node (ref "5V_LED") (pin "P$1") (pinfunction "A_P$1") (pintype "passive"))
      (node (ref "R31") (pin "1") (pinfunction "1_1") (pintype "passive"))
    )
    (net (code "45") (name "Net-(5V_PG-PadA)") (class "Default")
      (node (ref "5V_PG") (pin "A") (pinfunction "A_A") (pintype "passive"))
      (node (ref "R2") (pin "1") (pinfunction "1_1") (pintype "passive"))
    )
    (net (code "46") (name "Net-(5V_REG-BIAS)") (class "Default")
      (node (ref "5V_REG") (pin "1") (pinfunction "BIAS_1") (pintype "bidirectional"))
      (node (ref "C2") (pin "1") (pinfunction "1_1") (pintype "passive"))
      (node (ref "C42") (pin "1") (pinfunction "1_1") (pintype "passive"))
      (node (ref "C61") (pin "1") (pinfunction "1_1") (pintype "passive"))
      (node (ref "C62") (pin "P$1") (pinfunction "+_P$1") (pintype "passive"))
      (node (ref "L1") (pin "P$2") (pinfunction "2_P$2") (pintype "passive"))
      (node (ref "R23") (pin "2") (pinfunction "2_2") (pintype "passive"))
      (node (ref "U$2") (pin "P$1") (pinfunction "IP+_P$1") (pintype "bidirectional"))
      (node (ref "U$2") (pin "P$2") (pinfunction "IP+_P$2") (pintype "bidirectional"))
      (node (ref "U$2") (pin "P$8") (pinfunction "VCC_P$8") (pintype "bidirectional"))
    )
    (net (code "47") (name "Net-(5V_REG-BST)") (class "Default")
      (node (ref "5V_REG") (pin "3") (pinfunction "BST_3") (pintype "bidirectional"))
      (node (ref "C65") (pin "1") (pinfunction "1_1") (pintype "passive"))
    )
    (net (code "48") (name "Net-(5V_REG-FB)") (class "Default")
      (node (ref "5V_REG") (pin "20") (pinfunction "FB_20") (pintype "bidirectional"))
      (node (ref "C42") (pin "2") (pinfunction "2_2") (pintype "passive"))
      (node (ref "R23") (pin "1") (pinfunction "1_1") (pintype "passive"))
      (node (ref "R24") (pin "2") (pinfunction "2_2") (pintype "passive"))
    )
    (net (code "49") (name "Net-(5V_REG-INTV-CC)") (class "Default")
      (node (ref "5V_REG") (pin "2") (pinfunction "INTV-CC_2") (pintype "bidirectional"))
      (node (ref "C63") (pin "1") (pinfunction "1_1") (pintype "passive"))
    )
    (net (code "50") (name "Net-(5V_REG-PG)") (class "Default")
      (node (ref "5V_REG") (pin "19") (pinfunction "PG_19") (pintype "bidirectional"))
      (node (ref "R3") (pin "1") (pinfunction "1_1") (pintype "passive"))
      (node (ref "U$1") (pin "P$1") (pinfunction "G_P$1") (pintype "bidirectional"))
    )
    (net (code "51") (name "Net-(5V_REG-RT)") (class "Default")
      (node (ref "5V_REG") (pin "15") (pinfunction "RT_15") (pintype "bidirectional"))
      (node (ref "R17") (pin "2") (pinfunction "2_2") (pintype "passive"))
    )
    (net (code "52") (name "Net-(5V_VOLTAGE-IN+)") (class "Default")
      (node (ref "5V_VOLTAGE") (pin "P$1") (pinfunction "IN+_P$1") (pintype "bidirectional"))
      (node (ref "5V_VOLTAGE") (pin "P$2") (pinfunction "IN-_P$2") (pintype "bidirectional"))
      (node (ref "R35") (pin "2") (pinfunction "2_2") (pintype "passive"))
    )
    (net (code "53") (name "Net-(12V_CURR_ADC-VIN)") (class "Default")
      (node (ref "12V_CURR_ADC") (pin "P$4") (pinfunction "VIN_P$4") (pintype "bidirectional"))
      (node (ref "U$35") (pin "P$7") (pinfunction "VIOUT_P$7") (pintype "bidirectional"))
    )
    (net (code "54") (name "Net-(12V_LED-A)") (class "Default")
      (node (ref "12V_LED") (pin "P$1") (pinfunction "A_P$1") (pintype "passive"))
      (node (ref "R33") (pin "1") (pinfunction "1_1") (pintype "passive"))
    )
    (net (code "55") (name "Net-(12V_REG-BIAS)") (class "Default")
      (node (ref "12V_REG") (pin "1") (pinfunction "BIAS_1") (pintype "bidirectional"))
      (node (ref "C28") (pin "1") (pinfunction "1_1") (pintype "passive"))
      (node (ref "C35") (pin "1") (pinfunction "1_1") (pintype "passive"))
      (node (ref "C36") (pin "P$1") (pinfunction "+_P$1") (pintype "passive"))
      (node (ref "L2") (pin "P$2") (pinfunction "2_P$2") (pintype "passive"))
      (node (ref "R15") (pin "2") (pinfunction "2_2") (pintype "passive"))
      (node (ref "U$35") (pin "P$1") (pinfunction "IP+_P$1") (pintype "bidirectional"))
      (node (ref "U$35") (pin "P$2") (pinfunction "IP+_P$2") (pintype "bidirectional"))
    )
    (net (code "56") (name "Net-(12V_REG-BST)") (class "Default")
      (node (ref "12V_REG") (pin "3") (pinfunction "BST_3") (pintype "bidirectional"))
      (node (ref "C41") (pin "1") (pinfunction "1_1") (pintype "passive"))
    )
    (net (code "57") (name "Net-(12V_REG-FB)") (class "Default")
      (node (ref "12V_REG") (pin "20") (pinfunction "FB_20") (pintype "bidirectional"))
      (node (ref "C28") (pin "2") (pinfunction "2_2") (pintype "passive"))
      (node (ref "R15") (pin "1") (pinfunction "1_1") (pintype "passive"))
      (node (ref "R16") (pin "2") (pinfunction "2_2") (pintype "passive"))
    )
    (net (code "58") (name "Net-(12V_REG-INTV-CC)") (class "Default")
      (node (ref "12V_REG") (pin "2") (pinfunction "INTV-CC_2") (pintype "bidirectional"))
      (node (ref "C39") (pin "1") (pinfunction "1_1") (pintype "passive"))
    )
    (net (code "59") (name "Net-(12V_REG-PG)") (class "Default")
      (node (ref "12V_REG") (pin "19") (pinfunction "PG_19") (pintype "bidirectional"))
      (node (ref "R40") (pin "1") (pinfunction "1_1") (pintype "passive"))
      (node (ref "U$66") (pin "P$1") (pinfunction "G_P$1") (pintype "bidirectional"))
    )
    (net (code "60") (name "Net-(12V_REG-RT)") (class "Default")
      (node (ref "12V_REG") (pin "15") (pinfunction "RT_15") (pintype "bidirectional"))
      (node (ref "R14") (pin "2") (pinfunction "2_2") (pintype "passive"))
    )
    (net (code "61") (name "Net-(12V_VOLTAGE-IN+)") (class "Default")
      (node (ref "12V_VOLTAGE") (pin "P$1") (pinfunction "IN+_P$1") (pintype "bidirectional"))
      (node (ref "12V_VOLTAGE") (pin "P$2") (pinfunction "IN-_P$2") (pintype "bidirectional"))
      (node (ref "R25") (pin "2") (pinfunction "2_2") (pintype "passive"))
    )
    (net (code "62") (name "Net-(I2C_SHIFT-EN)") (class "Default")
      (node (ref "C23") (pin "1") (pinfunction "1_1") (pintype "passive"))
      (node (ref "I2C_SHIFT") (pin "P$7") (pinfunction "VREF2_P$7") (pintype "bidirectional"))
      (node (ref "I2C_SHIFT") (pin "P$8") (pinfunction "EN_P$8") (pintype "bidirectional"))
      (node (ref "R12") (pin "1") (pinfunction "1_1") (pintype "passive"))
    )
    (net (code "63") (name "Net-(L1-1)") (class "Default")
      (node (ref "5V_REG") (pin "21") (pinfunction "SW_21") (pintype "bidirectional"))
      (node (ref "5V_REG") (pin "22") (pinfunction "SW_22") (pintype "bidirectional"))
      (node (ref "5V_REG") (pin "8") (pinfunction "SW_8") (pintype "bidirectional"))
      (node (ref "5V_REG") (pin "9") (pinfunction "SW_9") (pintype "bidirectional"))
      (node (ref "C65") (pin "2") (pinfunction "2_2") (pintype "passive"))
      (node (ref "L1") (pin "P$1") (pinfunction "1_P$1") (pintype "passive"))
    )
    (net (code "64") (name "Net-(L2-1)") (class "Default")
      (node (ref "12V_REG") (pin "21") (pinfunction "SW_21") (pintype "bidirectional"))
      (node (ref "12V_REG") (pin "22") (pinfunction "SW_22") (pintype "bidirectional"))
      (node (ref "12V_REG") (pin "8") (pinfunction "SW_8") (pintype "bidirectional"))
      (node (ref "12V_REG") (pin "9") (pinfunction "SW_9") (pintype "bidirectional"))
      (node (ref "C41") (pin "2") (pinfunction "2_2") (pintype "passive"))
      (node (ref "L2") (pin "P$1") (pinfunction "1_P$1") (pintype "passive"))
    )
    (net (code "65") (name "Net-(LED2-PadA)") (class "Default")
      (node (ref "LED2") (pin "A") (pinfunction "A_A") (pintype "passive"))
      (node (ref "R38") (pin "1") (pinfunction "1_1") (pintype "passive"))
    )
    (net (code "66") (name "Net-(U$1-D)") (class "Default")
      (node (ref "R2") (pin "2") (pinfunction "2_2") (pintype "passive"))
      (node (ref "U$1") (pin "P$2") (pinfunction "D_P$2") (pintype "bidirectional"))
    )
    (net (code "67") (name "Net-(U$2-FILTER)") (class "Default")
      (node (ref "C3") (pin "1") (pinfunction "1_1") (pintype "passive"))
      (node (ref "U$2") (pin "P$6") (pinfunction "FILTER_P$6") (pintype "bidirectional"))
    )
    (net (code "68") (name "Net-(U$2-IP--PadP$3)") (class "Default")
      (node (ref "U$2") (pin "P$3") (pinfunction "IP-_P$3") (pintype "bidirectional"))
      (node (ref "U$2") (pin "P$4") (pinfunction "IP-_P$4") (pintype "bidirectional"))
      (node (ref "U$20") (pin "P$1") (pinfunction "P$1_P$1") (pintype "bidirectional"))
    )
    (net (code "69") (name "Net-(U$3-~{RESET})") (class "Default")
      (node (ref "R1") (pin "1") (pinfunction "1_1") (pintype "passive"))
      (node (ref "U$3") (pin "2-5") (pinfunction "~{RESET}_2-5") (pintype "bidirectional"))
    )
    (net (code "70") (name "Net-(U$4-FILTER)") (class "Default")
      (node (ref "C6") (pin "1") (pinfunction "1_1") (pintype "passive"))
      (node (ref "U$4") (pin "P$6") (pinfunction "FILTER_P$6") (pintype "bidirectional"))
    )
    (net (code "71") (name "Net-(U$4-IP--PadP$3)") (class "Default")
      (node (ref "U$4") (pin "P$3") (pinfunction "IP-_P$3") (pintype "bidirectional"))
      (node (ref "U$4") (pin "P$4") (pinfunction "IP-_P$4") (pintype "bidirectional"))
      (node (ref "U$6") (pin "P$1") (pinfunction "P$1_P$1") (pintype "bidirectional"))
    )
    (net (code "72") (name "Net-(U$8-FILTER)") (class "Default")
      (node (ref "C9") (pin "1") (pinfunction "1_1") (pintype "passive"))
      (node (ref "U$8") (pin "P$6") (pinfunction "FILTER_P$6") (pintype "bidirectional"))
    )
    (net (code "73") (name "Net-(U$8-IP--PadP$3)") (class "Default")
      (node (ref "U$8") (pin "P$3") (pinfunction "IP-_P$3") (pintype "bidirectional"))
      (node (ref "U$8") (pin "P$4") (pinfunction "IP-_P$4") (pintype "bidirectional"))
      (node (ref "U$9") (pin "P$1") (pinfunction "P$1_P$1") (pintype "bidirectional"))
    )
    (net (code "74") (name "Net-(U$10-C)") (class "Default")
      (node (ref "C52") (pin "1") (pinfunction "1_1") (pintype "passive"))
      (node (ref "C58") (pin "1") (pinfunction "1_1") (pintype "passive"))
      (node (ref "THRUST8") (pin "P$4") (pinfunction "P$4_P$4") (pintype "bidirectional"))
      (node (ref "U$10") (pin "P$2") (pinfunction "C_P$2") (pintype "passive"))
      (node (ref "U$40") (pin "P$2") (pinfunction "P$2_P$2") (pintype "bidirectional"))
    )
    (net (code "75") (name "Net-(U$11-FILTER)") (class "Default")
      (node (ref "C12") (pin "1") (pinfunction "1_1") (pintype "passive"))
      (node (ref "U$11") (pin "P$6") (pinfunction "FILTER_P$6") (pintype "bidirectional"))
    )
    (net (code "76") (name "Net-(U$11-IP--PadP$3)") (class "Default")
      (node (ref "U$11") (pin "P$3") (pinfunction "IP-_P$3") (pintype "bidirectional"))
      (node (ref "U$11") (pin "P$4") (pinfunction "IP-_P$4") (pintype "bidirectional"))
      (node (ref "U$12") (pin "P$1") (pinfunction "P$1_P$1") (pintype "bidirectional"))
    )
    (net (code "77") (name "Net-(U$13-C)") (class "Default")
      (node (ref "C30") (pin "1") (pinfunction "1_1") (pintype "passive"))
      (node (ref "C90") (pin "1") (pinfunction "1_1") (pintype "passive"))
      (node (ref "THRUST6") (pin "P$4") (pinfunction "P$4_P$4") (pintype "bidirectional"))
      (node (ref "U$13") (pin "P$2") (pinfunction "C_P$2") (pintype "passive"))
      (node (ref "U$27") (pin "P$2") (pinfunction "P$2_P$2") (pintype "bidirectional"))
    )
    (net (code "78") (name "Net-(U$14-FILTER)") (class "Default")
      (node (ref "C15") (pin "1") (pinfunction "1_1") (pintype "passive"))
      (node (ref "U$14") (pin "P$6") (pinfunction "FILTER_P$6") (pintype "bidirectional"))
    )
    (net (code "79") (name "Net-(U$14-IP--PadP$3)") (class "Default")
      (node (ref "U$14") (pin "P$3") (pinfunction "IP-_P$3") (pintype "bidirectional"))
      (node (ref "U$14") (pin "P$4") (pinfunction "IP-_P$4") (pintype "bidirectional"))
      (node (ref "U$15") (pin "P$1") (pinfunction "P$1_P$1") (pintype "bidirectional"))
    )
    (net (code "80") (name "Net-(U$16-C)") (class "Default")
      (node (ref "C55") (pin "1") (pinfunction "1_1") (pintype "passive"))
      (node (ref "C92") (pin "1") (pinfunction "1_1") (pintype "passive"))
      (node (ref "THRUST7") (pin "P$4") (pinfunction "P$4_P$4") (pintype "bidirectional"))
      (node (ref "U$16") (pin "P$2") (pinfunction "C_P$2") (pintype "passive"))
      (node (ref "U$37") (pin "P$2") (pinfunction "P$2_P$2") (pintype "bidirectional"))
    )
    (net (code "81") (name "Net-(U$17-FILTER)") (class "Default")
      (node (ref "C18") (pin "1") (pinfunction "1_1") (pintype "passive"))
      (node (ref "U$17") (pin "P$6") (pinfunction "FILTER_P$6") (pintype "bidirectional"))
    )
    (net (code "82") (name "Net-(U$17-IP--PadP$3)") (class "Default")
      (node (ref "U$17") (pin "P$3") (pinfunction "IP-_P$3") (pintype "bidirectional"))
      (node (ref "U$17") (pin "P$4") (pinfunction "IP-_P$4") (pintype "bidirectional"))
      (node (ref "U$18") (pin "P$1") (pinfunction "P$1_P$1") (pintype "bidirectional"))
    )
    (net (code "83") (name "Net-(U$19-FILTER)") (class "Default")
      (node (ref "C20") (pin "1") (pinfunction "1_1") (pintype "passive"))
      (node (ref "U$19") (pin "P$6") (pinfunction "FILTER_P$6") (pintype "bidirectional"))
    )
    (net (code "84") (name "Net-(U$19-IP--PadP$3)") (class "Default")
      (node (ref "U$19") (pin "P$3") (pinfunction "IP-_P$3") (pintype "bidirectional"))
      (node (ref "U$19") (pin "P$4") (pinfunction "IP-_P$4") (pintype "bidirectional"))
      (node (ref "U$5") (pin "P$1") (pinfunction "P$1_P$1") (pintype "bidirectional"))
      (node (ref "U$5") (pin "P$2") (pinfunction "P$1_P$2") (pintype "bidirectional"))
    )
    (net (code "85") (name "Net-(U$19-VIOUT)") (class "Default")
      (node (ref "U$19") (pin "P$7") (pinfunction "VIOUT_P$7") (pintype "bidirectional"))
      (node (ref "V-THRUST_CURR_ADC") (pin "P$4") (pinfunction "VIN_P$4") (pintype "bidirectional"))
    )
    (net (code "86") (name "Net-(U$22-C)") (class "Default")
      (node (ref "C21") (pin "1") (pinfunction "1_1") (pintype "passive"))
      (node (ref "C91") (pin "1") (pinfunction "1_1") (pintype "passive"))
      (node (ref "THRUST5") (pin "P$4") (pinfunction "P$4_P$4") (pintype "bidirectional"))
      (node (ref "U$18") (pin "P$2") (pinfunction "P$2_P$2") (pintype "bidirectional"))
      (node (ref "U$22") (pin "P$2") (pinfunction "C_P$2") (pintype "passive"))
    )
    (net (code "87") (name "Net-(U$23-FILTER)") (class "Default")
      (node (ref "C29") (pin "1") (pinfunction "1_1") (pintype "passive"))
      (node (ref "U$23") (pin "P$6") (pinfunction "FILTER_P$6") (pintype "bidirectional"))
    )
    (net (code "88") (name "Net-(U$23-IP--PadP$3)") (class "Default")
      (node (ref "U$23") (pin "P$3") (pinfunction "IP-_P$3") (pintype "bidirectional"))
      (node (ref "U$23") (pin "P$4") (pinfunction "IP-_P$4") (pintype "bidirectional"))
      (node (ref "U$27") (pin "P$1") (pinfunction "P$1_P$1") (pintype "bidirectional"))
    )
    (net (code "89") (name "Net-(U$26-C)") (class "Default")
      (node (ref "C13") (pin "1") (pinfunction "1_1") (pintype "passive"))
      (node (ref "C87") (pin "1") (pinfunction "1_1") (pintype "passive"))
      (node (ref "THRUST3") (pin "P$4") (pinfunction "P$4_P$4") (pintype "bidirectional"))
      (node (ref "U$12") (pin "P$2") (pinfunction "P$2_P$2") (pintype "bidirectional"))
      (node (ref "U$26") (pin "P$2") (pinfunction "C_P$2") (pintype "passive"))
    )
    (net (code "90") (name "Net-(U$28-C)") (class "Default")
      (node (ref "C16") (pin "1") (pinfunction "1_1") (pintype "passive"))
      (node (ref "C89") (pin "1") (pinfunction "1_1") (pintype "passive"))
      (node (ref "THRUST4") (pin "P$4") (pinfunction "P$4_P$4") (pintype "bidirectional"))
      (node (ref "U$15") (pin "P$2") (pinfunction "P$2_P$2") (pintype "bidirectional"))
      (node (ref "U$28") (pin "P$2") (pinfunction "C_P$2") (pintype "passive"))
    )
    (net (code "91") (name "Net-(U$29-FILTER)") (class "Default")
      (node (ref "C37") (pin "1") (pinfunction "1_1") (pintype "passive"))
      (node (ref "U$29") (pin "P$6") (pinfunction "FILTER_P$6") (pintype "bidirectional"))
    )
    (net (code "92") (name "Net-(U$29-IP--PadP$3)") (class "Default")
      (node (ref "U$29") (pin "P$3") (pinfunction "IP-_P$3") (pintype "bidirectional"))
      (node (ref "U$29") (pin "P$4") (pinfunction "IP-_P$4") (pintype "bidirectional"))
      (node (ref "U$37") (pin "P$1") (pinfunction "P$1_P$1") (pintype "bidirectional"))
    )
    (net (code "93") (name "Net-(U$30-C)") (class "Default")
      (node (ref "C10") (pin "1") (pinfunction "1_1") (pintype "passive"))
      (node (ref "C88") (pin "1") (pinfunction "1_1") (pintype "passive"))
      (node (ref "THRUST2") (pin "P$4") (pinfunction "P$4_P$4") (pintype "bidirectional"))
      (node (ref "U$30") (pin "P$2") (pinfunction "C_P$2") (pintype "passive"))
      (node (ref "U$9") (pin "P$2") (pinfunction "P$2_P$2") (pintype "bidirectional"))
    )
    (net (code "94") (name "Net-(U$31-C)") (class "Default")
      (node (ref "C54") (pin "1") (pinfunction "1_1") (pintype "passive"))
      (node (ref "C86") (pin "1") (pinfunction "1_1") (pintype "passive"))
      (node (ref "THRUST1") (pin "P$4") (pinfunction "P$4_P$4") (pintype "bidirectional"))
      (node (ref "U$31") (pin "P$2") (pinfunction "C_P$2") (pintype "passive"))
      (node (ref "U$6") (pin "P$2") (pinfunction "P$2_P$2") (pintype "bidirectional"))
    )
    (net (code "95") (name "Net-(U$35-FILTER)") (class "Default")
      (node (ref "C31") (pin "1") (pinfunction "1_1") (pintype "passive"))
      (node (ref "U$35") (pin "P$6") (pinfunction "FILTER_P$6") (pintype "bidirectional"))
    )
    (net (code "96") (name "Net-(U$35-IP--PadP$3)") (class "Default")
      (node (ref "U$35") (pin "P$3") (pinfunction "IP-_P$3") (pintype "bidirectional"))
      (node (ref "U$35") (pin "P$4") (pinfunction "IP-_P$4") (pintype "bidirectional"))
      (node (ref "U$36") (pin "P$1") (pinfunction "P$1_P$1") (pintype "bidirectional"))
    )
    (net (code "97") (name "Net-(U$39-FILTER)") (class "Default")
      (node (ref "C57") (pin "1") (pinfunction "1_1") (pintype "passive"))
      (node (ref "U$39") (pin "P$6") (pinfunction "FILTER_P$6") (pintype "bidirectional"))
    )
    (net (code "98") (name "Net-(U$39-IP--PadP$3)") (class "Default")
      (node (ref "U$39") (pin "P$3") (pinfunction "IP-_P$3") (pintype "bidirectional"))
      (node (ref "U$39") (pin "P$4") (pinfunction "IP-_P$4") (pintype "bidirectional"))
      (node (ref "U$40") (pin "P$1") (pinfunction "P$1_P$1") (pintype "bidirectional"))
    )
    (net (code "99") (name "Net-(U$45-IN)") (class "Default")
      (node (ref "C32") (pin "1") (pinfunction "1_1") (pintype "passive"))
      (node (ref "R18") (pin "2") (pinfunction "2_2") (pintype "passive"))
      (node (ref "U$45") (pin "P$2") (pinfunction "IN_P$2") (pintype "bidirectional"))
    )
    (net (code "100") (name "Net-(U$59-C)") (class "Default")
      (node (ref "CPU_ON") (pin "P$1") (pinfunction "P$1_P$1") (pintype "bidirectional"))
      (node (ref "R18") (pin "1") (pinfunction "1_1") (pintype "passive"))
      (node (ref "R21") (pin "1") (pinfunction "1_1") (pintype "passive"))
      (node (ref "U$59") (pin "P$2") (pinfunction "C_P$2") (pintype "passive"))
    )
    (net (code "101") (name "Net-(U$66-D)") (class "Default")
      (node (ref "R38") (pin "2") (pinfunction "2_2") (pintype "passive"))
      (node (ref "U$66") (pin "P$2") (pinfunction "D_P$2") (pintype "bidirectional"))
    )
    (net (code "102") (name "Net-(V-THRUST_LED-A)") (class "Default")
      (node (ref "R32") (pin "1") (pinfunction "1_1") (pintype "passive"))
      (node (ref "V-THRUST_LED") (pin "P$1") (pinfunction "A_P$1") (pintype "passive"))
    )
    (net (code "103") (name "Net-(V-THRUST_VOLTAGE-IN+)") (class "Default")
      (node (ref "R30") (pin "2") (pinfunction "2_2") (pintype "passive"))
      (node (ref "V-THRUST_VOLTAGE") (pin "P$1") (pinfunction "IN+_P$1") (pintype "bidirectional"))
      (node (ref "V-THRUST_VOLTAGE") (pin "P$2") (pinfunction "IN-_P$2") (pintype "bidirectional"))
    )
    (net (code "104") (name "unconnected-(5V_CURR_ADC-ALERT-PadP$2)") (class "Default")
      (node (ref "5V_CURR_ADC") (pin "P$2") (pinfunction "ALERT_P$2") (pintype "bidirectional"))
    )
    (net (code "105") (name "unconnected-(5V_REG-SYNC{slash}MODE-Pad17)") (class "Default")
      (node (ref "5V_REG") (pin "17") (pinfunction "SYNC/MODE_17") (pintype "bidirectional"))
    )
    (net (code "106") (name "unconnected-(5V_REG-TR{slash}SS-Pad16)") (class "Default")
      (node (ref "5V_REG") (pin "16") (pinfunction "TR/SS_16") (pintype "bidirectional"))
    )
    (net (code "107") (name "unconnected-(12V_CURR_ADC-ALERT-PadP$2)") (class "Default")
      (node (ref "12V_CURR_ADC") (pin "P$2") (pinfunction "ALERT_P$2") (pintype "bidirectional"))
    )
    (net (code "108") (name "unconnected-(12V_REG-SYNC{slash}MODE-Pad17)") (class "Default")
      (node (ref "12V_REG") (pin "17") (pinfunction "SYNC/MODE_17") (pintype "bidirectional"))
    )
    (net (code "109") (name "unconnected-(12V_REG-TR{slash}SS-Pad16)") (class "Default")
      (node (ref "12V_REG") (pin "16") (pinfunction "TR/SS_16") (pintype "bidirectional"))
    )
    (net (code "110") (name "unconnected-(U$3-PA2-Pad2-10)") (class "Default")
      (node (ref "U$3") (pin "2-10") (pinfunction "PA2_2-10") (pintype "bidirectional"))
    )
    (net (code "111") (name "unconnected-(U$3-PA3-Pad2-9)") (class "Default")
      (node (ref "U$3") (pin "2-9") (pinfunction "PA3_2-9") (pintype "bidirectional"))
    )
    (net (code "112") (name "unconnected-(U$3-PA4-Pad2-8)") (class "Default")
      (node (ref "U$3") (pin "2-8") (pinfunction "PA4_2-8") (pintype "bidirectional"))
    )
    (net (code "113") (name "unconnected-(U$3-PA5-Pad1-8)") (class "Default")
      (node (ref "U$3") (pin "1-8") (pinfunction "PA5_1-8") (pintype "bidirectional"))
    )
    (net (code "114") (name "unconnected-(U$3-PB2-Pad2-2)") (class "Default")
      (node (ref "U$3") (pin "2-2") (pinfunction "PB2_2-2") (pintype "bidirectional"))
    )
    (net (code "115") (name "unconnected-(U$3-PB3-Pad4-3)") (class "Default")
      (node (ref "U$3") (pin "4-3") (pinfunction "PB3_4-3") (pintype "bidirectional"))
    )
    (net (code "116") (name "unconnected-(U$3-PB6-Pad3-3)") (class "Default")
      (node (ref "U$3") (pin "3-3") (pinfunction "PB6_3-3") (pintype "bidirectional"))
    )
    (net (code "117") (name "unconnected-(U$3-PB7-Pad3-4)") (class "Default")
      (node (ref "U$3") (pin "3-4") (pinfunction "PB7_3-4") (pintype "bidirectional"))
    )
    (net (code "118") (name "unconnected-(U$3-PC4-Pad4-4)") (class "Default")
      (node (ref "U$3") (pin "4-4") (pinfunction "PC4_4-4") (pintype "bidirectional"))
    )
    (net (code "119") (name "unconnected-(U$3-PC5-Pad4-5)") (class "Default")
      (node (ref "U$3") (pin "4-5") (pinfunction "PC5_4-5") (pintype "bidirectional"))
    )
    (net (code "120") (name "unconnected-(U$3-PC6-Pad4-6)") (class "Default")
      (node (ref "U$3") (pin "4-6") (pinfunction "PC6_4-6") (pintype "bidirectional"))
    )
    (net (code "121") (name "unconnected-(U$3-PC7-Pad4-7)") (class "Default")
      (node (ref "U$3") (pin "4-7") (pinfunction "PC7_4-7") (pintype "bidirectional"))
    )
    (net (code "122") (name "unconnected-(U$3-PD6-Pad4-8)") (class "Default")
      (node (ref "U$3") (pin "4-8") (pinfunction "PD6_4-8") (pintype "bidirectional"))
    )
    (net (code "123") (name "unconnected-(U$3-PD7-Pad4-9)") (class "Default")
      (node (ref "U$3") (pin "4-9") (pinfunction "PD7_4-9") (pintype "bidirectional"))
    )
    (net (code "124") (name "unconnected-(U$3-PF0-Pad2-4)") (class "Default")
      (node (ref "U$3") (pin "2-4") (pinfunction "PF0_2-4") (pintype "bidirectional"))
    )
    (net (code "125") (name "unconnected-(U$3-PF1-Pad3-10)") (class "Default")
      (node (ref "U$3") (pin "3-10") (pinfunction "PF1_3-10") (pintype "bidirectional"))
    )
    (net (code "126") (name "unconnected-(U$3-PF2-Pad4-1)") (class "Default")
      (node (ref "U$3") (pin "4-1") (pinfunction "PF2_4-1") (pintype "bidirectional"))
    )
    (net (code "127") (name "unconnected-(U$3-PF3-Pad4-2)") (class "Default")
      (node (ref "U$3") (pin "4-2") (pinfunction "PF3_4-2") (pintype "bidirectional"))
    )
    (net (code "128") (name "unconnected-(U$3-PF4-Pad4-10)") (class "Default")
      (node (ref "U$3") (pin "4-10") (pinfunction "PF4_4-10") (pintype "bidirectional"))
    )
    (net (code "129") (name "unconnected-(U1-CH8-Pad15)") (class "Default")
      (node (ref "U1") (pin "15") (pinfunction "CH8_15") (pintype "bidirectional"))
    )
    (net (code "130") (name "unconnected-(U1-CH9-Pad16)") (class "Default")
      (node (ref "U1") (pin "16") (pinfunction "CH9_16") (pintype "bidirectional"))
    )
    (net (code "131") (name "unconnected-(U1-CH10-Pad17)") (class "Default")
      (node (ref "U1") (pin "17") (pinfunction "CH10_17") (pintype "bidirectional"))
    )
    (net (code "132") (name "unconnected-(U1-CH11-Pad18)") (class "Default")
      (node (ref "U1") (pin "18") (pinfunction "CH11_18") (pintype "bidirectional"))
    )
    (net (code "133") (name "unconnected-(U1-CH12-Pad19)") (class "Default")
      (node (ref "U1") (pin "19") (pinfunction "CH12_19") (pintype "bidirectional"))
    )
    (net (code "134") (name "unconnected-(U1-CH13-Pad20)") (class "Default")
      (node (ref "U1") (pin "20") (pinfunction "CH13_20") (pintype "bidirectional"))
    )
    (net (code "135") (name "unconnected-(U1-CH14-Pad21)") (class "Default")
      (node (ref "U1") (pin "21") (pinfunction "CH14_21") (pintype "bidirectional"))
    )
    (net (code "136") (name "unconnected-(U1-CH15-Pad22)") (class "Default")
      (node (ref "U1") (pin "22") (pinfunction "CH15_22") (pintype "bidirectional"))
    )
    (net (code "137") (name "unconnected-(V-THRUST_CURR_ADC-ALERT-PadP$2)") (class "Default")
      (node (ref "V-THRUST_CURR_ADC") (pin "P$2") (pinfunction "ALERT_P$2") (pintype "bidirectional"))
    )
  )
)
